# EtherMegaR3.net
KiCad netlist of a schematic drawn in EAGLE
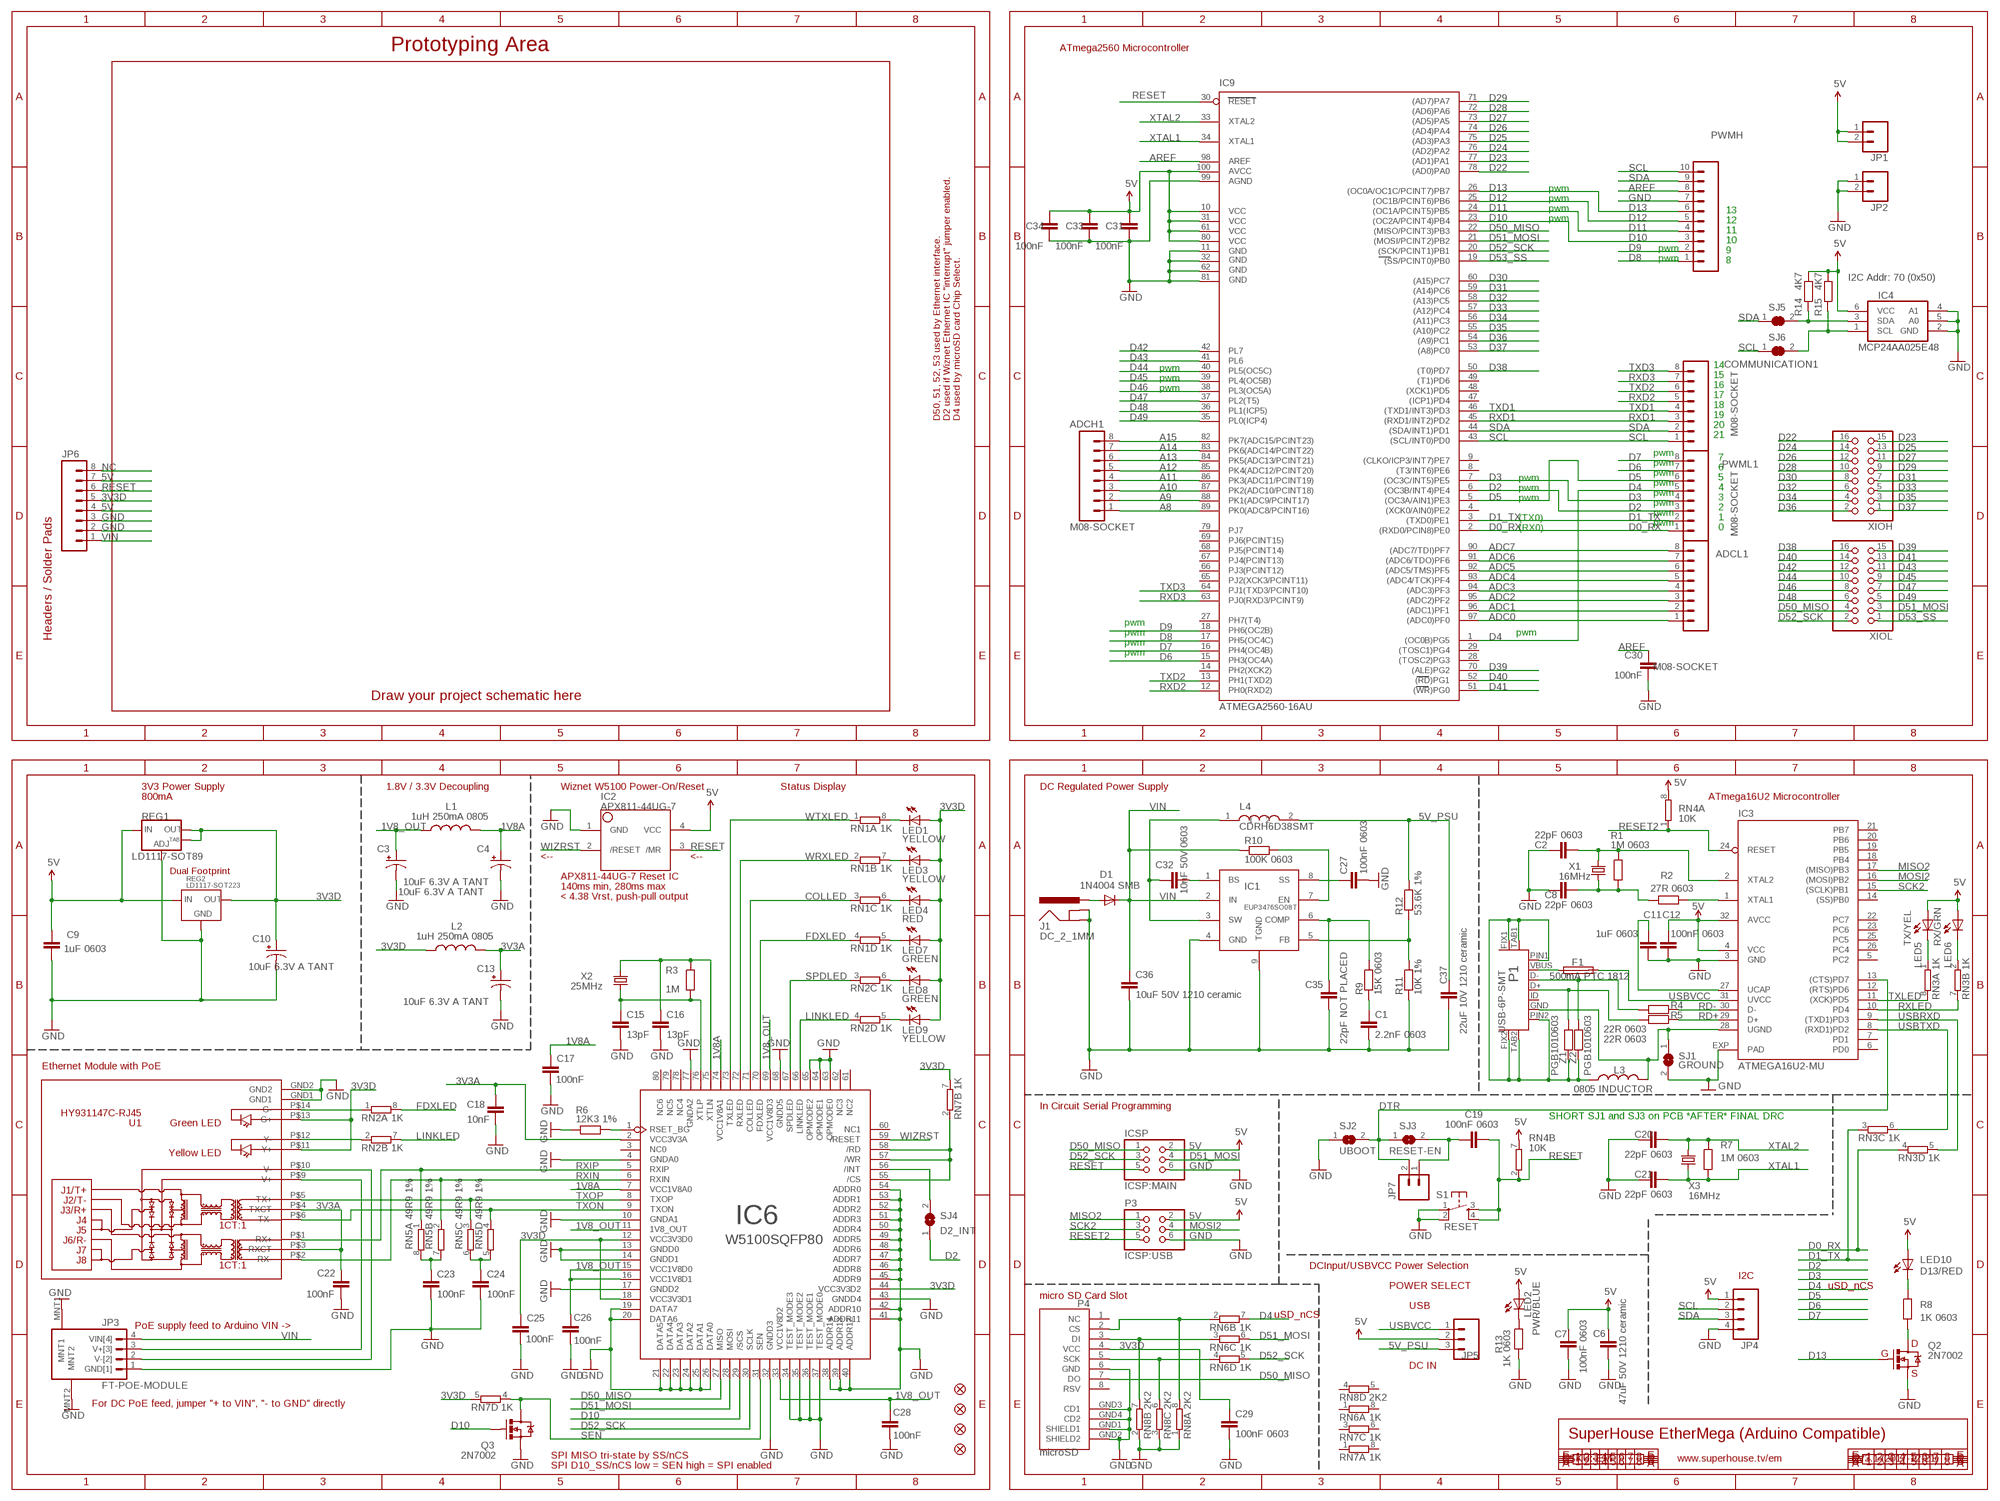
[diagram p0: schematic, sheet 1]

(export (version "E")
  (design (tool "Eeschema 10.0.6"))
  (components
    (comp (ref "ADCH1")
      (value "M08-SOCKET")
      (footprint "eagle-import:1X08-S")
      (libsource (lib "eagle-import") (part "M08-SOCKET"))
    )
    (comp (ref "ADCL1")
      (value "M08-SOCKET")
      (footprint "eagle-import:1X08-S")
      (libsource (lib "eagle-import") (part "M08-SOCKET"))
    )
    (comp (ref "C1")
      (value "2.2nF 0603")
      (footprint "eagle-import:C0603")
      (libsource (lib "eagle-import") (part "CAP0603"))
    )
    (comp (ref "C2")
      (value "22pF 0603")
      (footprint "eagle-import:C0603")
      (libsource (lib "eagle-import") (part "CAP0603"))
    )
    (comp (ref "C3")
      (value "10uF 6.3V A TANT")
      (footprint "eagle-import:EIA3216")
      (libsource (lib "eagle-import") (part "CAP_POL1206"))
    )
    (comp (ref "C4")
      (value "10uF 6.3V A TANT")
      (footprint "eagle-import:EIA3216")
      (libsource (lib "eagle-import") (part "CAP_POL1206"))
    )
    (comp (ref "C6")
      (value "47uF 50V 1210 ceramic")
      (footprint "eagle-import:C1210")
      (libsource (lib "eagle-import") (part "C-EUC1210"))
    )
    (comp (ref "C7")
      (value "100nF 0603")
      (footprint "eagle-import:C0603")
      (libsource (lib "eagle-import") (part "CAP0603"))
    )
    (comp (ref "C8")
      (value "22pF 0603")
      (footprint "eagle-import:C0603")
      (libsource (lib "eagle-import") (part "CAP0603"))
    )
    (comp (ref "C9")
      (value "1uF 0603")
      (footprint "eagle-import:C0603")
      (libsource (lib "eagle-import") (part "CAP0603"))
    )
    (comp (ref "C10")
      (value "10uF 6.3V A TANT")
      (footprint "eagle-import:EIA3216")
      (libsource (lib "eagle-import") (part "freetronics_CAP_POL1206"))
    )
    (comp (ref "C11")
      (value "1uF 0603")
      (footprint "eagle-import:C0603")
      (libsource (lib "eagle-import") (part "CAP0603"))
    )
    (comp (ref "C12")
      (value "100nF 0603")
      (footprint "eagle-import:C0603")
      (libsource (lib "eagle-import") (part "CAP0603"))
    )
    (comp (ref "C13")
      (value "10uF 6.3V A TANT")
      (footprint "eagle-import:EIA3216")
      (libsource (lib "eagle-import") (part "CAP_POL1206"))
    )
    (comp (ref "C15")
      (value "13pF")
      (footprint "eagle-import:C0603")
      (libsource (lib "eagle-import") (part "CAP0603"))
    )
    (comp (ref "C16")
      (value "13pF")
      (footprint "eagle-import:C0603")
      (libsource (lib "eagle-import") (part "CAP0603"))
    )
    (comp (ref "C17")
      (value "100nF")
      (footprint "eagle-import:C0603")
      (libsource (lib "eagle-import") (part "CAP0603"))
    )
    (comp (ref "C18")
      (value "10nF")
      (footprint "eagle-import:0603")
      (libsource (lib "eagle-import") (part "freetronics-marc_CAP0603"))
    )
    (comp (ref "C19")
      (value "100nF 0603")
      (footprint "eagle-import:C0603")
      (libsource (lib "eagle-import") (part "CAP0603"))
    )
    (comp (ref "C20")
      (value "22pF 0603")
      (footprint "eagle-import:C0603")
      (libsource (lib "eagle-import") (part "CAP0603"))
    )
    (comp (ref "C21")
      (value "22pF 0603")
      (footprint "eagle-import:C0603")
      (libsource (lib "eagle-import") (part "CAP0603"))
    )
    (comp (ref "C22")
      (value "100nF")
      (footprint "eagle-import:C0603")
      (libsource (lib "eagle-import") (part "CAP0603"))
    )
    (comp (ref "C23")
      (value "100nF")
      (footprint "eagle-import:C0603")
      (libsource (lib "eagle-import") (part "CAP0603"))
    )
    (comp (ref "C24")
      (value "100nF")
      (footprint "eagle-import:C0603")
      (libsource (lib "eagle-import") (part "CAP0603"))
    )
    (comp (ref "C25")
      (value "100nF")
      (footprint "eagle-import:C0603")
      (libsource (lib "eagle-import") (part "CAP0603"))
    )
    (comp (ref "C26")
      (value "100nF")
      (footprint "eagle-import:C0603")
      (libsource (lib "eagle-import") (part "CAP0603"))
    )
    (comp (ref "C27")
      (value "100nF 0603")
      (footprint "eagle-import:C0603")
      (libsource (lib "eagle-import") (part "CAP0603"))
    )
    (comp (ref "C28")
      (value "100nF")
      (footprint "eagle-import:C0603")
      (libsource (lib "eagle-import") (part "CAP0603"))
    )
    (comp (ref "C29")
      (value "100nF 0603")
      (footprint "eagle-import:C0603")
      (libsource (lib "eagle-import") (part "CAP0603"))
    )
    (comp (ref "C30")
      (value "100nF")
      (footprint "eagle-import:C0603")
      (libsource (lib "eagle-import") (part "CAP0603"))
    )
    (comp (ref "C31")
      (value "100nF")
      (footprint "eagle-import:C0603")
      (libsource (lib "eagle-import") (part "CAP0603"))
    )
    (comp (ref "C32")
      (value "10nF 50V 0603")
      (footprint "eagle-import:C0603")
      (libsource (lib "eagle-import") (part "CAP0603"))
    )
    (comp (ref "C33")
      (value "100nF")
      (footprint "eagle-import:C0603")
      (libsource (lib "eagle-import") (part "CAP0603"))
    )
    (comp (ref "C34")
      (value "100nF")
      (footprint "eagle-import:C0603")
      (libsource (lib "eagle-import") (part "CAP0603"))
    )
    (comp (ref "C35")
      (value "22pF NOT PLACED")
      (footprint "eagle-import:C0603")
      (libsource (lib "eagle-import") (part "CAP0603"))
    )
    (comp (ref "C36")
      (value "10uF 50V 1210 ceramic")
      (footprint "eagle-import:C1210")
      (libsource (lib "eagle-import") (part "C-EUC1210"))
    )
    (comp (ref "C37")
      (value "22uF 10V 1210 ceramic")
      (footprint "eagle-import:C1210")
      (libsource (lib "eagle-import") (part "C-EUC1210"))
    )
    (comp (ref "COMMUNICATION1")
      (value "M08-SOCKET")
      (footprint "eagle-import:1X08-S")
      (libsource (lib "eagle-import") (part "M08-SOCKET"))
    )
    (comp (ref "D1")
      (value "1N4004 SMB")
      (footprint "eagle-import:SMB-DIODE")
      (libsource (lib "eagle-import") (part "DIODESMB"))
    )
    (comp (ref "F1")
      (value "500mA PTC 1812")
      (footprint "eagle-import:1812")
      (libsource (lib "eagle-import") (part "PTC050"))
    )
    (comp (ref "FID1")
      (value "FIDUCIAL1X2.5")
      (footprint "eagle-import:FIDUCIAL-1X2.5")
      (libsource (lib "eagle-import") (part "FIDUCIAL1X2.5"))
    )
    (comp (ref "FID2")
      (value "FIDUCIAL1X2.5")
      (footprint "eagle-import:FIDUCIAL-1X2.5")
      (libsource (lib "eagle-import") (part "FIDUCIAL1X2.5"))
    )
    (comp (ref "FID3")
      (value "FIDUCIAL1X2.5")
      (footprint "eagle-import:FIDUCIAL-1X2.5")
      (libsource (lib "eagle-import") (part "FIDUCIAL1X2.5"))
    )
    (comp (ref "FID4")
      (value "FIDUCIAL1X2.5")
      (footprint "eagle-import:FIDUCIAL-1X2.5")
      (libsource (lib "eagle-import") (part "FIDUCIAL1X2.5"))
    )
    (comp (ref "IC1")
      (value "EUP3476SO08T")
      (footprint "eagle-import:SO08T")
      (libsource (lib "eagle-import") (part "EUP3476SO08T"))
    )
    (comp (ref "IC2")
      (value "APX811-44UG-7")
      (footprint "eagle-import:SOT143-R")
      (libsource (lib "eagle-import") (part "APX81X-RESET-IC"))
    )
    (comp (ref "IC3")
      (value "ATMEGA16U2-MU")
      (footprint "eagle-import:ATMEL_QFN32")
      (libsource (lib "eagle-import") (part "ATMEGA8U2QFN"))
    )
    (comp (ref "IC4")
      (value "MCP24AA025E48")
      (footprint "eagle-import:SOT23-6")
      (libsource (lib "eagle-import") (part "MCP24AA025E48"))
    )
    (comp (ref "IC6")
      (value "W5100SQFP80")
      (footprint "eagle-import:SQFP80")
      (libsource (lib "eagle-import") (part "W5100SQFP80"))
    )
    (comp (ref "IC9")
      (value "ATMEGA2560-16AU")
      (footprint "eagle-import:TQFP100")
      (libsource (lib "eagle-import") (part "ATMEGAAU1280-16"))
    )
    (comp (ref "ICSP")
      (value "ICSP:MAIN")
      (footprint "eagle-import:2X03")
      (libsource (lib "eagle-import") (part "PINHD-2X3"))
    )
    (comp (ref "J1")
      (value "DC_2_1MM")
      (footprint "eagle-import:POWER_JACK_SLOTS")
      (libsource (lib "eagle-import") (part "POWER_JACK-SLOTS"))
    )
    (comp (ref "JP1")
      (value "M02PTH")
      (footprint "eagle-import:1X02")
      (libsource (lib "eagle-import") (part "M02PTH"))
    )
    (comp (ref "JP2")
      (value "M02PTH")
      (footprint "eagle-import:1X02")
      (libsource (lib "eagle-import") (part "M02PTH"))
    )
    (comp (ref "JP3")
      (value "FT-POE-MODULE")
      (footprint "eagle-import:FT-POE-MODULE-CLEAN")
      (libsource (lib "eagle-import") (part "FT-POE-MODULE2"))
    )
    (comp (ref "JP4")
      (value "M04PTH")
      (footprint "eagle-import:1X04")
      (libsource (lib "eagle-import") (part "M04PTH"))
    )
    (comp (ref "JP5")
      (value "M03-PIN")
      (footprint "eagle-import:1X03-P")
      (libsource (lib "eagle-import") (part "M03-PIN"))
    )
    (comp (ref "JP6")
      (value "M08STD")
      (footprint "eagle-import:1X08")
      (libsource (lib "eagle-import") (part "M08STD"))
    )
    (comp (ref "JP7")
      (value "M02PTH")
      (footprint "eagle-import:1X02")
      (libsource (lib "eagle-import") (part "freetronics-master-v1.1_M02PTH"))
    )
    (comp (ref "L1")
      (value "1uH 250mA 0805")
      (footprint "eagle-import:L2012C")
      (libsource (lib "eagle-import") (part "L-USL2012C"))
    )
    (comp (ref "L2")
      (value "1uH 250mA 0805")
      (footprint "eagle-import:L2012C")
      (libsource (lib "eagle-import") (part "L-USL2012C"))
    )
    (comp (ref "L3")
      (value "0805 INDUCTOR")
      (footprint "eagle-import:0805-LARGE")
      (libsource (lib "eagle-import") (part "INDUCTOR0805-LARGE"))
    )
    (comp (ref "L4")
      (value "CDRH6D38SMT")
      (footprint "eagle-import:CDRH")
      (libsource (lib "eagle-import") (part "CDRH6D38SMT"))
    )
    (comp (ref "LED1")
      (value "YELLOW")
      (footprint "eagle-import:LED-0603")
      (libsource (lib "eagle-import") (part "LED0603"))
    )
    (comp (ref "LED2")
      (value "PWR/BLUE")
      (footprint "eagle-import:LED-0603")
      (libsource (lib "eagle-import") (part "LED0603"))
    )
    (comp (ref "LED3")
      (value "YELLOW")
      (footprint "eagle-import:LED-0603")
      (libsource (lib "eagle-import") (part "LED0603"))
    )
    (comp (ref "LED4")
      (value "RED")
      (footprint "eagle-import:LED-0603")
      (libsource (lib "eagle-import") (part "LED0603"))
    )
    (comp (ref "LED5")
      (value "TX/YEL")
      (footprint "eagle-import:LED-0603")
      (libsource (lib "eagle-import") (part "LED0603"))
    )
    (comp (ref "LED6")
      (value "RX/GRN")
      (footprint "eagle-import:LED-0603")
      (libsource (lib "eagle-import") (part "LED0603"))
    )
    (comp (ref "LED7")
      (value "GREEN")
      (footprint "eagle-import:LED-0603")
      (libsource (lib "eagle-import") (part "LED0603"))
    )
    (comp (ref "LED8")
      (value "GREEN")
      (footprint "eagle-import:LED-0603")
      (libsource (lib "eagle-import") (part "LED0603"))
    )
    (comp (ref "LED9")
      (value "YELLOW")
      (footprint "eagle-import:LED-0603")
      (libsource (lib "eagle-import") (part "LED0603"))
    )
    (comp (ref "LED10")
      (value "D13/RED")
      (footprint "eagle-import:LED-0603")
      (libsource (lib "eagle-import") (part "LED0603"))
    )
    (comp (ref "P1")
      (value "USB-6P-SMT")
      (footprint "eagle-import:USB-MICROB-MB05PMXX")
      (libsource (lib "eagle-import") (part "USB-6P-SMT"))
    )
    (comp (ref "P3")
      (value "ICSP:USB")
      (footprint "eagle-import:2X03")
      (libsource (lib "eagle-import") (part "PINHD-2X3"))
    )
    (comp (ref "P4")
      (value "microSD")
      (footprint "eagle-import:MOLEX-SD-500901-003")
      (libsource (lib "eagle-import") (part "USD-SOCKETHINGE"))
    )
    (comp (ref "PWMH")
      (value "M100.1")
      (footprint "eagle-import:1X10")
      (libsource (lib "eagle-import") (part "M100.1"))
    )
    (comp (ref "PWML1")
      (value "M08-SOCKET")
      (footprint "eagle-import:1X08-S")
      (libsource (lib "eagle-import") (part "M08-SOCKET"))
    )
    (comp (ref "Q2")
      (value "2N7002")
      (footprint "eagle-import:SOT23-3")
      (libsource (lib "eagle-import") (part "MOSFET-NCHANNEL-233"))
    )
    (comp (ref "Q3")
      (value "2N7002")
      (footprint "eagle-import:SOT23-3")
      (libsource (lib "eagle-import") (part "MOSFET-NCHANNEL-233"))
    )
    (comp (ref "R1")
      (value "1M 0603")
      (footprint "eagle-import:R0603")
      (libsource (lib "eagle-import") (part "RESISTOR0603"))
    )
    (comp (ref "R2")
      (value "27R 0603")
      (footprint "eagle-import:R0603")
      (libsource (lib "eagle-import") (part "RESISTOR0603"))
    )
    (comp (ref "R3")
      (value "1M")
      (footprint "eagle-import:R0603")
      (libsource (lib "eagle-import") (part "RESISTOR0603"))
    )
    (comp (ref "R4")
      (value "22R 0603")
      (footprint "eagle-import:R0603")
      (libsource (lib "eagle-import") (part "RESISTOR0603"))
    )
    (comp (ref "R5")
      (value "22R 0603")
      (footprint "eagle-import:R0603")
      (libsource (lib "eagle-import") (part "RESISTOR0603"))
    )
    (comp (ref "R6")
      (value "12K3 1%")
      (footprint "eagle-import:R0603")
      (libsource (lib "eagle-import") (part "RESISTOR0603"))
    )
    (comp (ref "R7")
      (value "1M 0603")
      (footprint "eagle-import:R0603")
      (libsource (lib "eagle-import") (part "RESISTOR0603"))
    )
    (comp (ref "R8")
      (value "1K 0603")
      (footprint "eagle-import:R0603")
      (libsource (lib "eagle-import") (part "RESISTOR0603"))
    )
    (comp (ref "R9")
      (value "15K 0603")
      (footprint "eagle-import:R0603")
      (libsource (lib "eagle-import") (part "RESISTOR0603"))
    )
    (comp (ref "R10")
      (value "100K 0603")
      (footprint "eagle-import:R0603")
      (libsource (lib "eagle-import") (part "RESISTOR0603"))
    )
    (comp (ref "R11")
      (value "10K 1%")
      (footprint "eagle-import:R0603")
      (libsource (lib "eagle-import") (part "RESISTOR0603"))
    )
    (comp (ref "R12")
      (value "53.6K 1%")
      (footprint "eagle-import:0603")
      (libsource (lib "eagle-import") (part "freetronics-original_RESISTOR0603"))
    )
    (comp (ref "R13")
      (value "1K 0603")
      (footprint "eagle-import:R0603")
      (libsource (lib "eagle-import") (part "RESISTOR0603"))
    )
    (comp (ref "R14")
      (value "4K7")
      (footprint "eagle-import:R0603")
      (libsource (lib "eagle-import") (part "RESISTOR0603"))
    )
    (comp (ref "R15")
      (value "4K7")
      (footprint "eagle-import:R0603")
      (libsource (lib "eagle-import") (part "RESISTOR0603"))
    )
    (comp (ref "REG1")
      (value "LD1117-SOT89")
      (footprint "eagle-import:SOT89")
      (libsource (lib "eagle-import") (part "V_REG_LM1117SOT89"))
    )
    (comp (ref "REG2")
      (value "LD1117-SOT223")
      (footprint "eagle-import:SOT-223")
      (libsource (lib "eagle-import") (part "LD1117"))
    )
    (comp (ref "RN1")
      (value "1K")
      (footprint "eagle-import:CAY16")
      (libsource (lib "eagle-import") (part "4R-NCAY16"))
    )
    (comp (ref "RN2")
      (value "1K")
      (footprint "eagle-import:CAY16")
      (libsource (lib "eagle-import") (part "4R-NCAY16"))
    )
    (comp (ref "RN3")
      (value "1K")
      (footprint "eagle-import:CAY16")
      (libsource (lib "eagle-import") (part "4R-NCAY16"))
    )
    (comp (ref "RN4")
      (value "10K")
      (footprint "eagle-import:CAY16")
      (libsource (lib "eagle-import") (part "freetronics-master-v1_4R-NCAY16"))
    )
    (comp (ref "RN5")
      (value "49R9 1%")
      (footprint "eagle-import:CAY16")
      (libsource (lib "eagle-import") (part "4R-NCAY16"))
    )
    (comp (ref "RN6")
      (value "1K")
      (footprint "eagle-import:CAY16")
      (libsource (lib "eagle-import") (part "4R-NCAY16"))
    )
    (comp (ref "RN7")
      (value "1K")
      (footprint "eagle-import:CAY16")
      (libsource (lib "eagle-import") (part "4R-NCAY16"))
    )
    (comp (ref "RN8")
      (value "2K2")
      (footprint "eagle-import:CAY16")
      (libsource (lib "eagle-import") (part "4R-NCAY16"))
    )
    (comp (ref "S1")
      (value "RESET")
      (footprint "eagle-import:TACTILE_SMD-6MM")
      (libsource (lib "eagle-import") (part "TAC_SWITCH-SMT-6"))
    )
    (comp (ref "SJ1")
      (value "GROUND")
      (footprint "eagle-import:SJ")
      (libsource (lib "eagle-import") (part "SJ"))
    )
    (comp (ref "SJ2")
      (value "UBOOT")
      (footprint "eagle-import:SJ")
      (libsource (lib "eagle-import") (part "SJ"))
    )
    (comp (ref "SJ3")
      (value "RESET-EN")
      (footprint "eagle-import:SJ")
      (libsource (lib "eagle-import") (part "SJ"))
    )
    (comp (ref "SJ4")
      (value "D2_INT")
      (footprint "eagle-import:SJ")
      (libsource (lib "eagle-import") (part "SJ"))
    )
    (comp (ref "SJ5")
      (value "SJCN")
      (footprint "eagle-import:SJC")
      (libsource (lib "eagle-import") (part "SJCN"))
    )
    (comp (ref "SJ6")
      (value "SJCN")
      (footprint "eagle-import:SJC")
      (libsource (lib "eagle-import") (part "SJCN"))
    )
    (comp (ref "U1")
      (value "HY931147C-RJ45")
      (footprint "eagle-import:HY931147C")
      (libsource (lib "eagle-import") (part "HY931147C-RJ45"))
    )
    (comp (ref "X1")
      (value "16MHz")
      (footprint "eagle-import:HC49U-V")
      (libsource (lib "eagle-import") (part "CRYSTALHC49UV"))
    )
    (comp (ref "X2")
      (value "25MHz")
      (footprint "eagle-import:HC49U-V")
      (libsource (lib "eagle-import") (part "CRYSTALHC49UV"))
    )
    (comp (ref "X3")
      (value "16MHz")
      (footprint "eagle-import:HC49U-V")
      (libsource (lib "eagle-import") (part "CRYSTALHC49UV"))
    )
    (comp (ref "XIOH")
      (value "PINHD-2X8")
      (footprint "eagle-import:2X08")
      (libsource (lib "eagle-import") (part "PINHD-2X8"))
    )
    (comp (ref "XIOL")
      (value "PINHD-2X8")
      (footprint "eagle-import:2X08")
      (libsource (lib "eagle-import") (part "PINHD-2X8"))
    )
    (comp (ref "Z1")
      (value "PGB1010603")
      (footprint "eagle-import:0603")
      (libsource (lib "eagle-import") (part "freetronics_RESISTOR0603"))
    )
    (comp (ref "Z2")
      (value "PGB1010603")
      (footprint "eagle-import:0603")
      (libsource (lib "eagle-import") (part "freetronics_RESISTOR0603"))
    )
  )
  (nets
    (net (code "1") (name "/1V8A") (class "Default")
      (node (ref "C17") (pin "1") (pinfunction "1_1") (pintype "passive"))
      (node (ref "C4") (pin "A") (pinfunction "+_A") (pintype "passive"))
      (node (ref "IC6") (pin "7") (pinfunction "VCC1V8A0_7") (pintype "bidirectional"))
      (node (ref "IC6") (pin "74") (pinfunction "VCC1V8A1_74") (pintype "bidirectional"))
      (node (ref "L1") (pin "2") (pinfunction "2_2") (pintype "passive"))
    )
    (net (code "2") (name "/1V8_OUT") (class "Default")
      (node (ref "C26") (pin "1") (pinfunction "1_1") (pintype "passive"))
      (node (ref "C28") (pin "1") (pinfunction "1_1") (pintype "passive"))
      (node (ref "C3") (pin "A") (pinfunction "+_A") (pintype "passive"))
      (node (ref "IC6") (pin "11") (pinfunction "1V8_OUT_11") (pintype "bidirectional"))
      (node (ref "IC6") (pin "15") (pinfunction "VCC1V8D0_15") (pintype "bidirectional"))
      (node (ref "IC6") (pin "16") (pinfunction "VCC1V8D1_16") (pintype "bidirectional"))
      (node (ref "IC6") (pin "33") (pinfunction "VCC1V8D2_33") (pintype "bidirectional"))
      (node (ref "IC6") (pin "69") (pinfunction "VCC1V8D3_69") (pintype "bidirectional"))
      (node (ref "L1") (pin "1") (pinfunction "1_1") (pintype "passive"))
    )
    (net (code "3") (name "/3V3A") (class "Default")
      (node (ref "C13") (pin "A") (pinfunction "+_A") (pintype "passive"))
      (node (ref "C18") (pin "1") (pinfunction "1_1") (pintype "passive"))
      (node (ref "C22") (pin "1") (pinfunction "1_1") (pintype "passive"))
      (node (ref "IC6") (pin "2") (pinfunction "VCC3V3A_2") (pintype "bidirectional"))
      (node (ref "L2") (pin "2") (pinfunction "2_2") (pintype "passive"))
      (node (ref "U1") (pin "P$3") (pinfunction "RXCT_P$3") (pintype "bidirectional"))
      (node (ref "U1") (pin "P$4") (pinfunction "TXCT_P$4") (pintype "bidirectional"))
    )
    (net (code "4") (name "/3V3D") (class "Default")
      (node (ref "C10") (pin "A") (pinfunction "+_A") (pintype "passive"))
      (node (ref "C25") (pin "1") (pinfunction "1_1") (pintype "passive"))
      (node (ref "C29") (pin "1") (pinfunction "1_1") (pintype "passive"))
      (node (ref "IC6") (pin "12") (pinfunction "VCC3V3D0_12") (pintype "bidirectional"))
      (node (ref "IC6") (pin "18") (pinfunction "VCC3V3D1_18") (pintype "bidirectional"))
      (node (ref "IC6") (pin "44") (pinfunction "VCC3V3D2_44") (pintype "bidirectional"))
      (node (ref "JP6") (pin "5") (pinfunction "5_5") (pintype "passive"))
      (node (ref "L2") (pin "1") (pinfunction "1_1") (pintype "passive"))
      (node (ref "LED1") (pin "A") (pinfunction "A_A") (pintype "passive"))
      (node (ref "LED3") (pin "A") (pinfunction "A_A") (pintype "passive"))
      (node (ref "LED4") (pin "A") (pinfunction "A_A") (pintype "passive"))
      (node (ref "LED7") (pin "A") (pinfunction "A_A") (pintype "passive"))
      (node (ref "LED8") (pin "A") (pinfunction "A_A") (pintype "passive"))
      (node (ref "LED9") (pin "A") (pinfunction "A_A") (pintype "passive"))
      (node (ref "P4") (pin "4") (pinfunction "VCC_4") (pintype "bidirectional"))
      (node (ref "REG1") (pin "2") (pinfunction "OUT_2") (pintype "output"))
      (node (ref "REG1") (pin "4") (pinfunction "OUT_4") (pintype "output"))
      (node (ref "REG2") (pin "2") (pinfunction "OUT_2") (pintype "power_in"))
      (node (ref "REG2") (pin "4") (pinfunction "OUT_4") (pintype "power_in"))
      (node (ref "RN7") (pin "5") (pinfunction "2_5") (pintype "passive"))
      (node (ref "RN7") (pin "7") (pinfunction "2_7") (pintype "passive"))
      (node (ref "U1") (pin "P$11") (pinfunction "Y+_P$11") (pintype "bidirectional"))
      (node (ref "U1") (pin "P$13") (pinfunction "G+_P$13") (pintype "bidirectional"))
    )
    (net (code "5") (name "/5V_PSU") (class "Default")
      (node (ref "C37") (pin "1") (pinfunction "1_1") (pintype "passive"))
      (node (ref "JP5") (pin "3") (pinfunction "3_3") (pintype "passive"))
      (node (ref "L4") (pin "2") (pinfunction "2_2") (pintype "bidirectional"))
      (node (ref "R12") (pin "2") (pinfunction "2_2") (pintype "passive"))
    )
    (net (code "6") (name "/A8") (class "Default")
      (node (ref "ADCH1") (pin "1") (pinfunction "1_1") (pintype "passive"))
      (node (ref "IC9") (pin "89") (pinfunction "PK0(ADC8/PCINT16)_89") (pintype "bidirectional"))
    )
    (net (code "7") (name "/A9") (class "Default")
      (node (ref "ADCH1") (pin "2") (pinfunction "2_2") (pintype "passive"))
      (node (ref "IC9") (pin "88") (pinfunction "PK1(ADC9/PCINT17)_88") (pintype "bidirectional"))
    )
    (net (code "8") (name "/A10") (class "Default")
      (node (ref "ADCH1") (pin "3") (pinfunction "3_3") (pintype "passive"))
      (node (ref "IC9") (pin "87") (pinfunction "PK2(ADC10/PCINT18)_87") (pintype "bidirectional"))
    )
    (net (code "9") (name "/A11") (class "Default")
      (node (ref "ADCH1") (pin "4") (pinfunction "4_4") (pintype "passive"))
      (node (ref "IC9") (pin "86") (pinfunction "PK3(ADC11/PCINT19)_86") (pintype "bidirectional"))
    )
    (net (code "10") (name "/A12") (class "Default")
      (node (ref "ADCH1") (pin "5") (pinfunction "5_5") (pintype "passive"))
      (node (ref "IC9") (pin "85") (pinfunction "PK4(ADC12/PCINT20)_85") (pintype "bidirectional"))
    )
    (net (code "11") (name "/A13") (class "Default")
      (node (ref "ADCH1") (pin "6") (pinfunction "6_6") (pintype "passive"))
      (node (ref "IC9") (pin "84") (pinfunction "PK5(ADC13/PCINT21)_84") (pintype "bidirectional"))
    )
    (net (code "12") (name "/A14") (class "Default")
      (node (ref "ADCH1") (pin "7") (pinfunction "7_7") (pintype "passive"))
      (node (ref "IC9") (pin "83") (pinfunction "PK6(ADC14/PCINT22)_83") (pintype "bidirectional"))
    )
    (net (code "13") (name "/A15") (class "Default")
      (node (ref "ADCH1") (pin "8") (pinfunction "8_8") (pintype "passive"))
      (node (ref "IC9") (pin "82") (pinfunction "PK7(ADC15/PCINT23)_82") (pintype "bidirectional"))
    )
    (net (code "14") (name "/ADC0") (class "Default")
      (node (ref "ADCL1") (pin "1") (pinfunction "1_1") (pintype "passive"))
      (node (ref "IC9") (pin "97") (pinfunction "(ADC0)PF0_97") (pintype "bidirectional"))
    )
    (net (code "15") (name "/ADC1") (class "Default")
      (node (ref "ADCL1") (pin "2") (pinfunction "2_2") (pintype "passive"))
      (node (ref "IC9") (pin "96") (pinfunction "(ADC1)PF1_96") (pintype "bidirectional"))
    )
    (net (code "16") (name "/ADC2") (class "Default")
      (node (ref "ADCL1") (pin "3") (pinfunction "3_3") (pintype "passive"))
      (node (ref "IC9") (pin "95") (pinfunction "(ADC2)PF2_95") (pintype "bidirectional"))
    )
    (net (code "17") (name "/ADC3") (class "Default")
      (node (ref "ADCL1") (pin "4") (pinfunction "4_4") (pintype "passive"))
      (node (ref "IC9") (pin "94") (pinfunction "(ADC3)PF3_94") (pintype "bidirectional"))
    )
    (net (code "18") (name "/ADC4") (class "Default")
      (node (ref "ADCL1") (pin "5") (pinfunction "5_5") (pintype "passive"))
      (node (ref "IC9") (pin "93") (pinfunction "(ADC4/TCK)PF4_93") (pintype "bidirectional"))
    )
    (net (code "19") (name "/ADC5") (class "Default")
      (node (ref "ADCL1") (pin "6") (pinfunction "6_6") (pintype "passive"))
      (node (ref "IC9") (pin "92") (pinfunction "(ADC5/TMS)PF5_92") (pintype "bidirectional"))
    )
    (net (code "20") (name "/ADC6") (class "Default")
      (node (ref "ADCL1") (pin "7") (pinfunction "7_7") (pintype "passive"))
      (node (ref "IC9") (pin "91") (pinfunction "(ADC6/TDO)PF6_91") (pintype "bidirectional"))
    )
    (net (code "21") (name "/ADC7") (class "Default")
      (node (ref "ADCL1") (pin "8") (pinfunction "8_8") (pintype "passive"))
      (node (ref "IC9") (pin "90") (pinfunction "(ADC7/TDI)PF7_90") (pintype "bidirectional"))
    )
    (net (code "22") (name "/AREF") (class "Default")
      (node (ref "C30") (pin "1") (pinfunction "1_1") (pintype "passive"))
      (node (ref "IC9") (pin "98") (pinfunction "AREF_98") (pintype "bidirectional"))
      (node (ref "PWMH") (pin "8") (pinfunction "8_8") (pintype "passive"))
    )
    (net (code "23") (name "/COLLED") (class "Default")
      (node (ref "IC6") (pin "71") (pinfunction "COLLED_71") (pintype "bidirectional"))
      (node (ref "RN1") (pin "3") (pinfunction "1_3") (pintype "passive"))
    )
    (net (code "24") (name "/D0_RX") (class "Default")
      (node (ref "IC9") (pin "2") (pinfunction "(RXD0/PCIN8)PE0_2") (pintype "bidirectional"))
      (node (ref "PWML1") (pin "1") (pinfunction "1_1") (pintype "passive"))
      (node (ref "RN3") (pin "4") (pinfunction "1_4") (pintype "passive"))
    )
    (net (code "25") (name "/D1_TX") (class "Default")
      (node (ref "IC9") (pin "3") (pinfunction "(TXD0)PE1_3") (pintype "bidirectional"))
      (node (ref "PWML1") (pin "2") (pinfunction "2_2") (pintype "passive"))
      (node (ref "RN3") (pin "3") (pinfunction "1_3") (pintype "passive"))
    )
    (net (code "26") (name "/D2") (class "Default")
      (node (ref "IC9") (pin "6") (pinfunction "(OC3B/INT4)PE4_6") (pintype "bidirectional"))
      (node (ref "PWML1") (pin "3") (pinfunction "3_3") (pintype "passive"))
      (node (ref "SJ4") (pin "1") (pinfunction "1_1") (pintype "passive"))
    )
    (net (code "27") (name "/D3") (class "Default")
      (node (ref "IC9") (pin "7") (pinfunction "(OC3C/INT5)PE5_7") (pintype "bidirectional"))
      (node (ref "PWML1") (pin "4") (pinfunction "4_4") (pintype "passive"))
    )
    (net (code "28") (name "/D4") (class "Default")
      (node (ref "IC9") (pin "1") (pinfunction "(OC0B)PG5_1") (pintype "bidirectional"))
      (node (ref "PWML1") (pin "5") (pinfunction "5_5") (pintype "passive"))
      (node (ref "RN6") (pin "7") (pinfunction "2_7") (pintype "passive"))
    )
    (net (code "29") (name "/D5") (class "Default")
      (node (ref "IC9") (pin "5") (pinfunction "(OC3A/AIN1)PE3_5") (pintype "bidirectional"))
      (node (ref "PWML1") (pin "6") (pinfunction "6_6") (pintype "passive"))
    )
    (net (code "30") (name "/D6") (class "Default")
      (node (ref "IC9") (pin "15") (pinfunction "PH3(OC4A)_15") (pintype "bidirectional"))
      (node (ref "PWML1") (pin "7") (pinfunction "7_7") (pintype "passive"))
    )
    (net (code "31") (name "/D7") (class "Default")
      (node (ref "IC9") (pin "16") (pinfunction "PH4(OC4B)_16") (pintype "bidirectional"))
      (node (ref "PWML1") (pin "8") (pinfunction "8_8") (pintype "passive"))
    )
    (net (code "32") (name "/D8") (class "Default")
      (node (ref "IC9") (pin "17") (pinfunction "PH5(OC4C)_17") (pintype "bidirectional"))
      (node (ref "PWMH") (pin "1") (pinfunction "1_1") (pintype "passive"))
    )
    (net (code "33") (name "/D9") (class "Default")
      (node (ref "IC9") (pin "18") (pinfunction "PH6(OC2B)_18") (pintype "bidirectional"))
      (node (ref "PWMH") (pin "2") (pinfunction "2_2") (pintype "passive"))
    )
    (net (code "34") (name "/D10") (class "Default")
      (node (ref "IC6") (pin "29") (pinfunction "/SCS_29") (pintype "bidirectional"))
      (node (ref "IC9") (pin "23") (pinfunction "(OC2A/PCINT4)PB4_23") (pintype "bidirectional"))
      (node (ref "PWMH") (pin "3") (pinfunction "3_3") (pintype "passive"))
      (node (ref "Q3") (pin "1") (pinfunction "G_1") (pintype "passive"))
    )
    (net (code "35") (name "/D11") (class "Default")
      (node (ref "IC9") (pin "24") (pinfunction "(OC1A/PCINT5)PB5_24") (pintype "bidirectional"))
      (node (ref "PWMH") (pin "4") (pinfunction "4_4") (pintype "passive"))
    )
    (net (code "36") (name "/D12") (class "Default")
      (node (ref "IC9") (pin "25") (pinfunction "(OC1B/PCINT6)PB6_25") (pintype "bidirectional"))
      (node (ref "PWMH") (pin "5") (pinfunction "5_5") (pintype "passive"))
    )
    (net (code "37") (name "/D13") (class "Default")
      (node (ref "IC9") (pin "26") (pinfunction "(OC0A/OC1C/PCINT7)PB7_26") (pintype "bidirectional"))
      (node (ref "PWMH") (pin "6") (pinfunction "6_6") (pintype "passive"))
      (node (ref "Q2") (pin "1") (pinfunction "G_1") (pintype "passive"))
    )
    (net (code "38") (name "/D22") (class "Default")
      (node (ref "IC9") (pin "78") (pinfunction "(AD0)PA0_78") (pintype "bidirectional"))
      (node (ref "XIOH") (pin "16") (pinfunction "16_16") (pintype "passive"))
    )
    (net (code "39") (name "/D23") (class "Default")
      (node (ref "IC9") (pin "77") (pinfunction "(AD1)PA1_77") (pintype "bidirectional"))
      (node (ref "XIOH") (pin "15") (pinfunction "15_15") (pintype "passive"))
    )
    (net (code "40") (name "/D24") (class "Default")
      (node (ref "IC9") (pin "76") (pinfunction "(AD2)PA2_76") (pintype "bidirectional"))
      (node (ref "XIOH") (pin "14") (pinfunction "14_14") (pintype "passive"))
    )
    (net (code "41") (name "/D25") (class "Default")
      (node (ref "IC9") (pin "75") (pinfunction "(AD3)PA3_75") (pintype "bidirectional"))
      (node (ref "XIOH") (pin "13") (pinfunction "13_13") (pintype "passive"))
    )
    (net (code "42") (name "/D26") (class "Default")
      (node (ref "IC9") (pin "74") (pinfunction "(AD4)PA4_74") (pintype "bidirectional"))
      (node (ref "XIOH") (pin "12") (pinfunction "12_12") (pintype "passive"))
    )
    (net (code "43") (name "/D27") (class "Default")
      (node (ref "IC9") (pin "73") (pinfunction "(AD5)PA5_73") (pintype "bidirectional"))
      (node (ref "XIOH") (pin "11") (pinfunction "11_11") (pintype "passive"))
    )
    (net (code "44") (name "/D28") (class "Default")
      (node (ref "IC9") (pin "72") (pinfunction "(AD6)PA6_72") (pintype "bidirectional"))
      (node (ref "XIOH") (pin "10") (pinfunction "10_10") (pintype "passive"))
    )
    (net (code "45") (name "/D29") (class "Default")
      (node (ref "IC9") (pin "71") (pinfunction "(AD7)PA7_71") (pintype "bidirectional"))
      (node (ref "XIOH") (pin "9") (pinfunction "9_9") (pintype "passive"))
    )
    (net (code "46") (name "/D30") (class "Default")
      (node (ref "IC9") (pin "60") (pinfunction "(A15)PC7_60") (pintype "bidirectional"))
      (node (ref "XIOH") (pin "8") (pinfunction "8_8") (pintype "passive"))
    )
    (net (code "47") (name "/D31") (class "Default")
      (node (ref "IC9") (pin "59") (pinfunction "(A14)PC6_59") (pintype "bidirectional"))
      (node (ref "XIOH") (pin "7") (pinfunction "7_7") (pintype "passive"))
    )
    (net (code "48") (name "/D32") (class "Default")
      (node (ref "IC9") (pin "58") (pinfunction "(A13)PC5_58") (pintype "bidirectional"))
      (node (ref "XIOH") (pin "6") (pinfunction "6_6") (pintype "passive"))
    )
    (net (code "49") (name "/D33") (class "Default")
      (node (ref "IC9") (pin "57") (pinfunction "(A12)PC4_57") (pintype "bidirectional"))
      (node (ref "XIOH") (pin "5") (pinfunction "5_5") (pintype "passive"))
    )
    (net (code "50") (name "/D34") (class "Default")
      (node (ref "IC9") (pin "56") (pinfunction "(A11)PC3_56") (pintype "bidirectional"))
      (node (ref "XIOH") (pin "4") (pinfunction "4_4") (pintype "passive"))
    )
    (net (code "51") (name "/D35") (class "Default")
      (node (ref "IC9") (pin "55") (pinfunction "(A10)PC2_55") (pintype "bidirectional"))
      (node (ref "XIOH") (pin "3") (pinfunction "3_3") (pintype "passive"))
    )
    (net (code "52") (name "/D36") (class "Default")
      (node (ref "IC9") (pin "54") (pinfunction "(A9)PC1_54") (pintype "bidirectional"))
      (node (ref "XIOH") (pin "2") (pinfunction "2_2") (pintype "passive"))
    )
    (net (code "53") (name "/D37") (class "Default")
      (node (ref "IC9") (pin "53") (pinfunction "(A8)PC0_53") (pintype "bidirectional"))
      (node (ref "XIOH") (pin "1") (pinfunction "1_1") (pintype "passive"))
    )
    (net (code "54") (name "/D38") (class "Default")
      (node (ref "IC9") (pin "50") (pinfunction "(T0)PD7_50") (pintype "bidirectional"))
      (node (ref "XIOL") (pin "16") (pinfunction "16_16") (pintype "passive"))
    )
    (net (code "55") (name "/D39") (class "Default")
      (node (ref "IC9") (pin "70") (pinfunction "(ALE)PG2_70") (pintype "bidirectional"))
      (node (ref "XIOL") (pin "15") (pinfunction "15_15") (pintype "passive"))
    )
    (net (code "56") (name "/D40") (class "Default")
      (node (ref "IC9") (pin "52") (pinfunction "(RD)PG1_52") (pintype "bidirectional"))
      (node (ref "XIOL") (pin "14") (pinfunction "14_14") (pintype "passive"))
    )
    (net (code "57") (name "/D41") (class "Default")
      (node (ref "IC9") (pin "51") (pinfunction "(WR)PG0_51") (pintype "bidirectional"))
      (node (ref "XIOL") (pin "13") (pinfunction "13_13") (pintype "passive"))
    )
    (net (code "58") (name "/D42") (class "Default")
      (node (ref "IC9") (pin "42") (pinfunction "PL7_42") (pintype "bidirectional"))
      (node (ref "XIOL") (pin "12") (pinfunction "12_12") (pintype "passive"))
    )
    (net (code "59") (name "/D43") (class "Default")
      (node (ref "IC9") (pin "41") (pinfunction "PL6_41") (pintype "bidirectional"))
      (node (ref "XIOL") (pin "11") (pinfunction "11_11") (pintype "passive"))
    )
    (net (code "60") (name "/D44") (class "Default")
      (node (ref "IC9") (pin "40") (pinfunction "PL5(OC5C)_40") (pintype "bidirectional"))
      (node (ref "XIOL") (pin "10") (pinfunction "10_10") (pintype "passive"))
    )
    (net (code "61") (name "/D45") (class "Default")
      (node (ref "IC9") (pin "39") (pinfunction "PL4(OC5B)_39") (pintype "bidirectional"))
      (node (ref "XIOL") (pin "9") (pinfunction "9_9") (pintype "passive"))
    )
    (net (code "62") (name "/D46") (class "Default")
      (node (ref "IC9") (pin "38") (pinfunction "PL3(OC5A)_38") (pintype "bidirectional"))
      (node (ref "XIOL") (pin "8") (pinfunction "8_8") (pintype "passive"))
    )
    (net (code "63") (name "/D47") (class "Default")
      (node (ref "IC9") (pin "37") (pinfunction "PL2(T5)_37") (pintype "bidirectional"))
      (node (ref "XIOL") (pin "7") (pinfunction "7_7") (pintype "passive"))
    )
    (net (code "64") (name "/D48") (class "Default")
      (node (ref "IC9") (pin "36") (pinfunction "PL1(ICP5)_36") (pintype "bidirectional"))
      (node (ref "XIOL") (pin "6") (pinfunction "6_6") (pintype "passive"))
    )
    (net (code "65") (name "/D49") (class "Default")
      (node (ref "IC9") (pin "35") (pinfunction "PL0(ICP4)_35") (pintype "bidirectional"))
      (node (ref "XIOL") (pin "5") (pinfunction "5_5") (pintype "passive"))
    )
    (net (code "66") (name "/D50_MISO") (class "Default")
      (node (ref "IC6") (pin "27") (pinfunction "MISO_27") (pintype "bidirectional"))
      (node (ref "IC9") (pin "22") (pinfunction "(MISO/PCINT3)PB3_22") (pintype "bidirectional"))
      (node (ref "ICSP") (pin "1") (pinfunction "1_1") (pintype "passive"))
      (node (ref "P4") (pin "7") (pinfunction "DO_7") (pintype "bidirectional"))
      (node (ref "XIOL") (pin "4") (pinfunction "4_4") (pintype "passive"))
    )
    (net (code "67") (name "/D51_MOSI") (class "Default")
      (node (ref "IC6") (pin "28") (pinfunction "MOSI_28") (pintype "bidirectional"))
      (node (ref "IC9") (pin "21") (pinfunction "(MOSI/PCINT2)PB2_21") (pintype "bidirectional"))
      (node (ref "ICSP") (pin "4") (pinfunction "4_4") (pintype "passive"))
      (node (ref "RN6") (pin "6") (pinfunction "2_6") (pintype "passive"))
      (node (ref "XIOL") (pin "3") (pinfunction "3_3") (pintype "passive"))
    )
    (net (code "68") (name "/D52_SCK") (class "Default")
      (node (ref "IC6") (pin "30") (pinfunction "SCLK_30") (pintype "bidirectional"))
      (node (ref "IC9") (pin "20") (pinfunction "(SCK/PCINT1)PB1_20") (pintype "bidirectional"))
      (node (ref "ICSP") (pin "3") (pinfunction "3_3") (pintype "passive"))
      (node (ref "RN6") (pin "5") (pinfunction "2_5") (pintype "passive"))
      (node (ref "XIOL") (pin "2") (pinfunction "2_2") (pintype "passive"))
    )
    (net (code "69") (name "/D53_SS") (class "Default")
      (node (ref "IC9") (pin "19") (pinfunction "(SS/PCINT0)PB0_19") (pintype "bidirectional"))
      (node (ref "XIOL") (pin "1") (pinfunction "1_1") (pintype "passive"))
    )
    (net (code "70") (name "/DTR") (class "Default")
      (node (ref "IC3") (pin "13") (pinfunction "(CTS)PD7_13") (pintype "bidirectional"))
      (node (ref "JP7") (pin "2") (pinfunction "2_2") (pintype "passive"))
      (node (ref "SJ2") (pin "2") (pinfunction "2_2") (pintype "passive"))
      (node (ref "SJ3") (pin "1") (pinfunction "1_1") (pintype "passive"))
    )
    (net (code "71") (name "/FDXLED") (class "Default")
      (node (ref "IC6") (pin "70") (pinfunction "FDXLED_70") (pintype "bidirectional"))
      (node (ref "RN1") (pin "4") (pinfunction "1_4") (pintype "passive"))
      (node (ref "RN2") (pin "8") (pinfunction "2_8") (pintype "passive"))
    )
    (net (code "72") (name "/LINKLED") (class "Default")
      (node (ref "IC6") (pin "66") (pinfunction "LINKLED_66") (pintype "bidirectional"))
      (node (ref "RN2") (pin "4") (pinfunction "1_4") (pintype "passive"))
      (node (ref "RN2") (pin "7") (pinfunction "2_7") (pintype "passive"))
    )
    (net (code "73") (name "/MISO2") (class "Default")
      (node (ref "IC3") (pin "17") (pinfunction "(MISO)PB3_17") (pintype "bidirectional"))
      (node (ref "P3") (pin "1") (pinfunction "1_1") (pintype "passive"))
    )
    (net (code "74") (name "/MOSI2") (class "Default")
      (node (ref "IC3") (pin "16") (pinfunction "(MOSI)PB2_16") (pintype "bidirectional"))
      (node (ref "P3") (pin "4") (pinfunction "4_4") (pintype "passive"))
    )
    (net (code "75") (name "/NC") (class "Default")
      (node (ref "JP6") (pin "8") (pinfunction "8_8") (pintype "passive"))
    )
    (net (code "76") (name "/RD+") (class "Default")
      (node (ref "IC3") (pin "29") (pinfunction "D+_29") (pintype "bidirectional"))
      (node (ref "R5") (pin "1") (pinfunction "1_1") (pintype "passive"))
    )
    (net (code "77") (name "/RD-") (class "Default")
      (node (ref "IC3") (pin "30") (pinfunction "D-_30") (pintype "bidirectional"))
      (node (ref "R4") (pin "1") (pinfunction "1_1") (pintype "passive"))
    )
    (net (code "78") (name "/RESET") (class "Default")
      (node (ref "C19") (pin "2") (pinfunction "2_2") (pintype "passive"))
      (node (ref "IC2") (pin "3") (pinfunction "/MR_3") (pintype "input"))
      (node (ref "IC9") (pin "30") (pinfunction "RESET_30") (pintype "input"))
      (node (ref "ICSP") (pin "5") (pinfunction "5_5") (pintype "passive"))
      (node (ref "JP6") (pin "6") (pinfunction "6_6") (pintype "passive"))
      (node (ref "RN4") (pin "2") (pinfunction "1_2") (pintype "passive"))
      (node (ref "S1") (pin "3") (pinfunction "3_3") (pintype "passive"))
      (node (ref "S1") (pin "4") (pinfunction "4_4") (pintype "passive"))
    )
    (net (code "79") (name "/RESET2") (class "Default")
      (node (ref "IC3") (pin "24") (pinfunction "RESET_24") (pintype "input"))
      (node (ref "P3") (pin "5") (pinfunction "5_5") (pintype "passive"))
      (node (ref "RN4") (pin "1") (pinfunction "1_1") (pintype "passive"))
    )
    (net (code "80") (name "/RXD1") (class "Default")
      (node (ref "COMMUNICATION1") (pin "3") (pinfunction "3_3") (pintype "passive"))
      (node (ref "IC9") (pin "45") (pinfunction "(RXD1/INT2)PD2_45") (pintype "bidirectional"))
    )
    (net (code "81") (name "/RXD2") (class "Default")
      (node (ref "COMMUNICATION1") (pin "5") (pinfunction "5_5") (pintype "passive"))
      (node (ref "IC9") (pin "12") (pinfunction "PH0(RXD2)_12") (pintype "bidirectional"))
    )
    (net (code "82") (name "/RXD3") (class "Default")
      (node (ref "COMMUNICATION1") (pin "7") (pinfunction "7_7") (pintype "passive"))
      (node (ref "IC9") (pin "63") (pinfunction "PJ0(RXD3/PCINT9)_63") (pintype "bidirectional"))
    )
    (net (code "83") (name "/RXIN") (class "Default")
      (node (ref "IC6") (pin "6") (pinfunction "RXIN_6") (pintype "bidirectional"))
      (node (ref "RN5") (pin "2") (pinfunction "1_2") (pintype "passive"))
      (node (ref "U1") (pin "P$2") (pinfunction "RX-_P$2") (pintype "bidirectional"))
    )
    (net (code "84") (name "/RXIP") (class "Default")
      (node (ref "IC6") (pin "5") (pinfunction "RXIP_5") (pintype "bidirectional"))
      (node (ref "RN5") (pin "1") (pinfunction "1_1") (pintype "passive"))
      (node (ref "U1") (pin "P$1") (pinfunction "RX+_P$1") (pintype "bidirectional"))
    )
    (net (code "85") (name "/RXLED") (class "Default")
      (node (ref "IC3") (pin "10") (pinfunction "PD4_10") (pintype "bidirectional"))
      (node (ref "RN3") (pin "7") (pinfunction "2_7") (pintype "passive"))
    )
    (net (code "86") (name "/SCK2") (class "Default")
      (node (ref "IC3") (pin "15") (pinfunction "(SCLK)PB1_15") (pintype "bidirectional"))
      (node (ref "P3") (pin "3") (pinfunction "3_3") (pintype "passive"))
    )
    (net (code "87") (name "/SCL") (class "Default")
      (node (ref "COMMUNICATION1") (pin "1") (pinfunction "1_1") (pintype "passive"))
      (node (ref "IC9") (pin "43") (pinfunction "(SCL/INT0)PD0_43") (pintype "bidirectional"))
      (node (ref "JP4") (pin "2") (pinfunction "2_2") (pintype "passive"))
      (node (ref "PWMH") (pin "10") (pinfunction "10_10") (pintype "passive"))
      (node (ref "SJ6") (pin "1") (pinfunction "1_1") (pintype "passive"))
    )
    (net (code "88") (name "/SDA") (class "Default")
      (node (ref "COMMUNICATION1") (pin "2") (pinfunction "2_2") (pintype "passive"))
      (node (ref "IC9") (pin "44") (pinfunction "(SDA/INT1)PD1_44") (pintype "bidirectional"))
      (node (ref "JP4") (pin "3") (pinfunction "3_3") (pintype "passive"))
      (node (ref "PWMH") (pin "9") (pinfunction "9_9") (pintype "passive"))
      (node (ref "SJ5") (pin "1") (pinfunction "1_1") (pintype "passive"))
    )
    (net (code "89") (name "/SEN") (class "Default")
      (node (ref "IC6") (pin "31") (pinfunction "SEN_31") (pintype "bidirectional"))
      (node (ref "Q3") (pin "3") (pinfunction "D_3") (pintype "passive"))
      (node (ref "RN7") (pin "4") (pinfunction "1_4") (pintype "passive"))
    )
    (net (code "90") (name "/SPDLED") (class "Default")
      (node (ref "IC6") (pin "67") (pinfunction "SPDLED_67") (pintype "bidirectional"))
      (node (ref "RN2") (pin "3") (pinfunction "1_3") (pintype "passive"))
    )
    (net (code "91") (name "/TXD1") (class "Default")
      (node (ref "COMMUNICATION1") (pin "4") (pinfunction "4_4") (pintype "passive"))
      (node (ref "IC9") (pin "46") (pinfunction "(TXD1/INT3)PD3_46") (pintype "bidirectional"))
    )
    (net (code "92") (name "/TXD2") (class "Default")
      (node (ref "COMMUNICATION1") (pin "6") (pinfunction "6_6") (pintype "passive"))
      (node (ref "IC9") (pin "13") (pinfunction "PH1(TXD2)_13") (pintype "bidirectional"))
    )
    (net (code "93") (name "/TXD3") (class "Default")
      (node (ref "COMMUNICATION1") (pin "8") (pinfunction "8_8") (pintype "passive"))
      (node (ref "IC9") (pin "64") (pinfunction "PJ1(TXD3/PCINT10)_64") (pintype "bidirectional"))
    )
    (net (code "94") (name "/TXLED") (class "Default")
      (node (ref "IC3") (pin "11") (pinfunction "(XCK)PD5_11") (pintype "bidirectional"))
      (node (ref "RN3") (pin "8") (pinfunction "2_8") (pintype "passive"))
    )
    (net (code "95") (name "/TXON") (class "Default")
      (node (ref "IC6") (pin "9") (pinfunction "TXON_9") (pintype "bidirectional"))
      (node (ref "RN5") (pin "4") (pinfunction "1_4") (pintype "passive"))
      (node (ref "U1") (pin "P$6") (pinfunction "TX-_P$6") (pintype "bidirectional"))
    )
    (net (code "96") (name "/TXOP") (class "Default")
      (node (ref "IC6") (pin "8") (pinfunction "TXOP_8") (pintype "bidirectional"))
      (node (ref "RN5") (pin "3") (pinfunction "1_3") (pintype "passive"))
      (node (ref "U1") (pin "P$5") (pinfunction "TX+_P$5") (pintype "bidirectional"))
    )
    (net (code "97") (name "/USBRXD") (class "Default")
      (node (ref "IC3") (pin "9") (pinfunction "(TXD1)PD3_9") (pintype "bidirectional"))
      (node (ref "RN3") (pin "5") (pinfunction "2_5") (pintype "passive"))
    )
    (net (code "98") (name "/USBTXD") (class "Default")
      (node (ref "IC3") (pin "8") (pinfunction "(RXD1)PD2_8") (pintype "bidirectional"))
      (node (ref "RN3") (pin "6") (pinfunction "2_6") (pintype "passive"))
    )
    (net (code "99") (name "/USBVCC") (class "Default")
      (node (ref "F1") (pin "2") (pinfunction "2_2") (pintype "passive"))
      (node (ref "IC3") (pin "31") (pinfunction "UVCC_31") (pintype "power_in"))
      (node (ref "JP5") (pin "1") (pinfunction "1_1") (pintype "passive"))
    )
    (net (code "100") (name "/VIN") (class "Default")
      (node (ref "C36") (pin "1") (pinfunction "1_1") (pintype "passive"))
      (node (ref "D1") (pin "C") (pinfunction "C_C") (pintype "passive"))
      (node (ref "IC1") (pin "2") (pinfunction "IN_2") (pintype "power_in"))
      (node (ref "JP3") (pin "4") (pinfunction "VIN[4]_4") (pintype "passive"))
      (node (ref "JP6") (pin "1") (pinfunction "1_1") (pintype "passive"))
      (node (ref "R10") (pin "1") (pinfunction "1_1") (pintype "passive"))
    )
    (net (code "101") (name "/WIZRST") (class "Default")
      (node (ref "IC2") (pin "2") (pinfunction "/RESET_2") (pintype "output"))
      (node (ref "IC6") (pin "59") (pinfunction "/RESET_59") (pintype "bidirectional"))
    )
    (net (code "102") (name "/WRXLED") (class "Default")
      (node (ref "IC6") (pin "72") (pinfunction "RXLED_72") (pintype "bidirectional"))
      (node (ref "RN1") (pin "2") (pinfunction "1_2") (pintype "passive"))
    )
    (net (code "103") (name "/WTXLED") (class "Default")
      (node (ref "IC6") (pin "73") (pinfunction "TXLED_73") (pintype "bidirectional"))
      (node (ref "RN1") (pin "1") (pinfunction "1_1") (pintype "passive"))
    )
    (net (code "104") (name "/XTAL1") (class "Default")
      (node (ref "C21") (pin "2") (pinfunction "2_2") (pintype "passive"))
      (node (ref "IC9") (pin "34") (pinfunction "XTAL1_34") (pintype "input"))
      (node (ref "R7") (pin "1") (pinfunction "1_1") (pintype "passive"))
      (node (ref "X3") (pin "1") (pinfunction "1_1") (pintype "passive"))
    )
    (net (code "105") (name "/XTAL2") (class "Default")
      (node (ref "C20") (pin "2") (pinfunction "2_2") (pintype "passive"))
      (node (ref "IC9") (pin "33") (pinfunction "XTAL2_33") (pintype "output"))
      (node (ref "R7") (pin "2") (pinfunction "2_2") (pintype "passive"))
      (node (ref "X3") (pin "2") (pinfunction "2_2") (pintype "passive"))
    )
    (net (code "106") (name "5V") (class "Default")
      (node (ref "C12") (pin "1") (pinfunction "1_1") (pintype "passive"))
      (node (ref "C31") (pin "1") (pinfunction "1_1") (pintype "passive"))
      (node (ref "C33") (pin "1") (pinfunction "1_1") (pintype "passive"))
      (node (ref "C34") (pin "1") (pinfunction "1_1") (pintype "passive"))
      (node (ref "C6") (pin "2") (pinfunction "2_2") (pintype "passive"))
      (node (ref "C7") (pin "1") (pinfunction "1_1") (pintype "passive"))
      (node (ref "C9") (pin "1") (pinfunction "1_1") (pintype "passive"))
      (node (ref "IC2") (pin "4") (pinfunction "VCC_4") (pintype "power_in"))
      (node (ref "IC3") (pin "32") (pinfunction "AVCC_32") (pintype "power_in"))
      (node (ref "IC3") (pin "4") (pinfunction "VCC_4") (pintype "power_in"))
      (node (ref "IC4") (pin "6") (pinfunction "VCC_6") (pintype "power_in"))
      (node (ref "IC9") (pin "10") (pinfunction "VCC_10") (pintype "power_in"))
      (node (ref "IC9") (pin "100") (pinfunction "AVCC_100") (pintype "power_in"))
      (node (ref "IC9") (pin "31") (pinfunction "VCC1_31") (pintype "power_in"))
      (node (ref "IC9") (pin "61") (pinfunction "VCC2_61") (pintype "power_in"))
      (node (ref "IC9") (pin "80") (pinfunction "VCC3_80") (pintype "power_in"))
      (node (ref "ICSP") (pin "2") (pinfunction "2_2") (pintype "passive"))
      (node (ref "JP1") (pin "1") (pinfunction "1_1") (pintype "passive"))
      (node (ref "JP1") (pin "2") (pinfunction "2_2") (pintype "passive"))
      (node (ref "JP4") (pin "1") (pinfunction "1_1") (pintype "passive"))
      (node (ref "JP5") (pin "2") (pinfunction "2_2") (pintype "passive"))
      (node (ref "JP6") (pin "4") (pinfunction "4_4") (pintype "passive"))
      (node (ref "JP6") (pin "7") (pinfunction "7_7") (pintype "passive"))
      (node (ref "LED10") (pin "A") (pinfunction "A_A") (pintype "passive"))
      (node (ref "LED2") (pin "A") (pinfunction "A_A") (pintype "passive"))
      (node (ref "LED5") (pin "A") (pinfunction "A_A") (pintype "passive"))
      (node (ref "LED6") (pin "A") (pinfunction "A_A") (pintype "passive"))
      (node (ref "P3") (pin "2") (pinfunction "2_2") (pintype "passive"))
      (node (ref "R14") (pin "1") (pinfunction "1_1") (pintype "passive"))
      (node (ref "R15") (pin "1") (pinfunction "1_1") (pintype "passive"))
      (node (ref "REG1") (pin "3") (pinfunction "IN_3") (pintype "input"))
      (node (ref "REG2") (pin "3") (pinfunction "IN_3") (pintype "input"))
      (node (ref "RN4") (pin "7") (pinfunction "2_7") (pintype "passive"))
      (node (ref "RN4") (pin "8") (pinfunction "2_8") (pintype "passive"))
    )
    (net (code "107") (name "GND") (class "Default")
      (node (ref "C1") (pin "2") (pinfunction "2_2") (pintype "passive"))
      (node (ref "C10") (pin "C") (pinfunction "-_C") (pintype "passive"))
      (node (ref "C11") (pin "2") (pinfunction "2_2") (pintype "passive"))
      (node (ref "C12") (pin "2") (pinfunction "2_2") (pintype "passive"))
      (node (ref "C13") (pin "C") (pinfunction "-_C") (pintype "passive"))
      (node (ref "C15") (pin "2") (pinfunction "2_2") (pintype "passive"))
      (node (ref "C16") (pin "2") (pinfunction "2_2") (pintype "passive"))
      (node (ref "C17") (pin "2") (pinfunction "2_2") (pintype "passive"))
      (node (ref "C18") (pin "2") (pinfunction "2_2") (pintype "passive"))
      (node (ref "C2") (pin "1") (pinfunction "1_1") (pintype "passive"))
      (node (ref "C20") (pin "1") (pinfunction "1_1") (pintype "passive"))
      (node (ref "C21") (pin "1") (pinfunction "1_1") (pintype "passive"))
      (node (ref "C22") (pin "2") (pinfunction "2_2") (pintype "passive"))
      (node (ref "C23") (pin "2") (pinfunction "2_2") (pintype "passive"))
      (node (ref "C24") (pin "2") (pinfunction "2_2") (pintype "passive"))
      (node (ref "C25") (pin "2") (pinfunction "2_2") (pintype "passive"))
      (node (ref "C26") (pin "2") (pinfunction "2_2") (pintype "passive"))
      (node (ref "C27") (pin "2") (pinfunction "2_2") (pintype "passive"))
      (node (ref "C28") (pin "2") (pinfunction "2_2") (pintype "passive"))
      (node (ref "C29") (pin "2") (pinfunction "2_2") (pintype "passive"))
      (node (ref "C3") (pin "C") (pinfunction "-_C") (pintype "passive"))
      (node (ref "C30") (pin "2") (pinfunction "2_2") (pintype "passive"))
      (node (ref "C31") (pin "2") (pinfunction "2_2") (pintype "passive"))
      (node (ref "C33") (pin "2") (pinfunction "2_2") (pintype "passive"))
      (node (ref "C34") (pin "2") (pinfunction "2_2") (pintype "passive"))
      (node (ref "C35") (pin "2") (pinfunction "2_2") (pintype "passive"))
      (node (ref "C36") (pin "2") (pinfunction "2_2") (pintype "passive"))
      (node (ref "C37") (pin "2") (pinfunction "2_2") (pintype "passive"))
      (node (ref "C4") (pin "C") (pinfunction "-_C") (pintype "passive"))
      (node (ref "C6") (pin "1") (pinfunction "1_1") (pintype "passive"))
      (node (ref "C7") (pin "2") (pinfunction "2_2") (pintype "passive"))
      (node (ref "C8") (pin "1") (pinfunction "1_1") (pintype "passive"))
      (node (ref "C9") (pin "2") (pinfunction "2_2") (pintype "passive"))
      (node (ref "IC1") (pin "4") (pinfunction "GND_4") (pintype "power_in"))
      (node (ref "IC1") (pin "9") (pinfunction "TGND_9") (pintype "power_in"))
      (node (ref "IC2") (pin "1") (pinfunction "GND_1") (pintype "power_in"))
      (node (ref "IC3") (pin "3") (pinfunction "GND_3") (pintype "power_in"))
      (node (ref "IC3") (pin "EXP") (pinfunction "PAD_EXP") (pintype "power_in"))
      (node (ref "IC4") (pin "2") (pinfunction "GND_2") (pintype "power_in"))
      (node (ref "IC4") (pin "4") (pinfunction "A1_4") (pintype "input"))
      (node (ref "IC4") (pin "5") (pinfunction "A0_5") (pintype "input"))
      (node (ref "IC6") (pin "10") (pinfunction "GNDA1_10") (pintype "bidirectional"))
      (node (ref "IC6") (pin "13") (pinfunction "GNDD0_13") (pintype "bidirectional"))
      (node (ref "IC6") (pin "14") (pinfunction "GNDD1_14") (pintype "bidirectional"))
      (node (ref "IC6") (pin "17") (pinfunction "GNDD2_17") (pintype "bidirectional"))
      (node (ref "IC6") (pin "19") (pinfunction "DATA7_19") (pintype "bidirectional"))
      (node (ref "IC6") (pin "20") (pinfunction "DATA6_20") (pintype "bidirectional"))
      (node (ref "IC6") (pin "21") (pinfunction "DATA5_21") (pintype "bidirectional"))
      (node (ref "IC6") (pin "22") (pinfunction "DATA4_22") (pintype "bidirectional"))
      (node (ref "IC6") (pin "23") (pinfunction "DATA3_23") (pintype "bidirectional"))
      (node (ref "IC6") (pin "24") (pinfunction "DATA2_24") (pintype "bidirectional"))
      (node (ref "IC6") (pin "25") (pinfunction "DATA1_25") (pintype "bidirectional"))
      (node (ref "IC6") (pin "26") (pinfunction "DATA0_26") (pintype "bidirectional"))
      (node (ref "IC6") (pin "32") (pinfunction "GNDD3_32") (pintype "bidirectional"))
      (node (ref "IC6") (pin "34") (pinfunction "TEST_MODE3_34") (pintype "bidirectional"))
      (node (ref "IC6") (pin "35") (pinfunction "TEST_MODE2_35") (pintype "bidirectional"))
      (node (ref "IC6") (pin "36") (pinfunction "TEST_MODE1_36") (pintype "bidirectional"))
      (node (ref "IC6") (pin "37") (pinfunction "TEST_MODE0_37") (pintype "bidirectional"))
      (node (ref "IC6") (pin "38") (pinfunction "ADDR14_38") (pintype "bidirectional"))
      (node (ref "IC6") (pin "39") (pinfunction "ADDR13_39") (pintype "bidirectional"))
      (node (ref "IC6") (pin "4") (pinfunction "GNDA0_4") (pintype "bidirectional"))
      (node (ref "IC6") (pin "40") (pinfunction "ADDR12_40") (pintype "bidirectional"))
      (node (ref "IC6") (pin "41") (pinfunction "ADDR11_41") (pintype "bidirectional"))
      (node (ref "IC6") (pin "42") (pinfunction "ADDR10_42") (pintype "bidirectional"))
      (node (ref "IC6") (pin "43") (pinfunction "GNDD4_43") (pintype "bidirectional"))
      (node (ref "IC6") (pin "45") (pinfunction "ADDR9_45") (pintype "bidirectional"))
      (node (ref "IC6") (pin "46") (pinfunction "ADDR8_46") (pintype "bidirectional"))
      (node (ref "IC6") (pin "47") (pinfunction "ADDR7_47") (pintype "bidirectional"))
      (node (ref "IC6") (pin "48") (pinfunction "ADDR6_48") (pintype "bidirectional"))
      (node (ref "IC6") (pin "49") (pinfunction "ADDR5_49") (pintype "bidirectional"))
      (node (ref "IC6") (pin "50") (pinfunction "ADDR4_50") (pintype "bidirectional"))
      (node (ref "IC6") (pin "51") (pinfunction "ADDR3_51") (pintype "bidirectional"))
      (node (ref "IC6") (pin "52") (pinfunction "ADDR2_52") (pintype "bidirectional"))
      (node (ref "IC6") (pin "53") (pinfunction "ADDR1_53") (pintype "bidirectional"))
      (node (ref "IC6") (pin "54") (pinfunction "ADDR0_54") (pintype "bidirectional"))
      (node (ref "IC6") (pin "63") (pinfunction "OPMODE0_63") (pintype "bidirectional"))
      (node (ref "IC6") (pin "64") (pinfunction "OPMODE1_64") (pintype "bidirectional"))
      (node (ref "IC6") (pin "65") (pinfunction "OPMODE2_65") (pintype "bidirectional"))
      (node (ref "IC6") (pin "68") (pinfunction "GNDD5_68") (pintype "bidirectional"))
      (node (ref "IC6") (pin "77") (pinfunction "GNDA2_77") (pintype "bidirectional"))
      (node (ref "IC9") (pin "11") (pinfunction "GND_11") (pintype "power_in"))
      (node (ref "IC9") (pin "32") (pinfunction "GND1_32") (pintype "power_in"))
      (node (ref "IC9") (pin "62") (pinfunction "GND2_62") (pintype "power_in"))
      (node (ref "IC9") (pin "81") (pinfunction "GND3_81") (pintype "power_in"))
      (node (ref "IC9") (pin "99") (pinfunction "AGND_99") (pintype "power_in"))
      (node (ref "ICSP") (pin "6") (pinfunction "6_6") (pintype "passive"))
      (node (ref "J1") (pin "GND") (pinfunction "GND_GND") (pintype "bidirectional"))
      (node (ref "J1") (pin "GNDBREAK") (pinfunction "GNDBREAK_GNDBREAK") (pintype "bidirectional"))
      (node (ref "JP2") (pin "1") (pinfunction "1_1") (pintype "passive"))
      (node (ref "JP2") (pin "2") (pinfunction "2_2") (pintype "passive"))
      (node (ref "JP3") (pin "1") (pinfunction "GND[1]_1") (pintype "passive"))
      (node (ref "JP3") (pin "MNT1") (pinfunction "MNT1_MNT1") (pintype "passive"))
      (node (ref "JP3") (pin "MNT2") (pinfunction "MNT2_MNT2") (pintype "passive"))
      (node (ref "JP4") (pin "4") (pinfunction "4_4") (pintype "passive"))
      (node (ref "JP6") (pin "2") (pinfunction "2_2") (pintype "passive"))
      (node (ref "JP6") (pin "3") (pinfunction "3_3") (pintype "passive"))
      (node (ref "P3") (pin "6") (pinfunction "6_6") (pintype "passive"))
      (node (ref "P4") (pin "6") (pinfunction "GND_6") (pintype "bidirectional"))
      (node (ref "P4") (pin "GND1") (pinfunction "SHIELD1_GND1") (pintype "bidirectional"))
      (node (ref "P4") (pin "GND2") (pinfunction "SHIELD2_GND2") (pintype "bidirectional"))
      (node (ref "P4") (pin "GND3") (pinfunction "CD1_GND3") (pintype "bidirectional"))
      (node (ref "P4") (pin "GND4") (pinfunction "CD2_GND4") (pintype "bidirectional"))
      (node (ref "PWMH") (pin "7") (pinfunction "7_7") (pintype "passive"))
      (node (ref "Q2") (pin "2") (pinfunction "S_2") (pintype "passive"))
      (node (ref "Q3") (pin "2") (pinfunction "S_2") (pintype "passive"))
      (node (ref "R11") (pin "1") (pinfunction "1_1") (pintype "passive"))
      (node (ref "R13") (pin "1") (pinfunction "1_1") (pintype "passive"))
      (node (ref "R6") (pin "1") (pinfunction "1_1") (pintype "passive"))
      (node (ref "REG1") (pin "1") (pinfunction "ADJ_1") (pintype "input"))
      (node (ref "REG2") (pin "1") (pinfunction "GND_1") (pintype "input"))
      (node (ref "RN8") (pin "1") (pinfunction "1_1") (pintype "passive"))
      (node (ref "RN8") (pin "2") (pinfunction "1_2") (pintype "passive"))
      (node (ref "RN8") (pin "3") (pinfunction "1_3") (pintype "passive"))
      (node (ref "S1") (pin "1") (pinfunction "1_1") (pintype "passive"))
      (node (ref "S1") (pin "2") (pinfunction "2_2") (pintype "passive"))
      (node (ref "SJ1") (pin "2") (pinfunction "2_2") (pintype "passive"))
      (node (ref "SJ2") (pin "1") (pinfunction "1_1") (pintype "passive"))
      (node (ref "U1") (pin "GND1") (pinfunction "GND1_GND1") (pintype "bidirectional"))
      (node (ref "U1") (pin "GND2") (pinfunction "GND2_GND2") (pintype "bidirectional"))
    )
    (net (code "108") (name "Net-(C1-Pad1)") (class "Default")
      (node (ref "C1") (pin "1") (pinfunction "1_1") (pintype "passive"))
      (node (ref "R9") (pin "1") (pinfunction "1_1") (pintype "passive"))
    )
    (net (code "109") (name "Net-(C8-Pad2)") (class "Default")
      (node (ref "C8") (pin "2") (pinfunction "2_2") (pintype "passive"))
      (node (ref "R1") (pin "1") (pinfunction "1_1") (pintype "passive"))
      (node (ref "R2") (pin "2") (pinfunction "2_2") (pintype "passive"))
      (node (ref "X1") (pin "1") (pinfunction "1_1") (pintype "passive"))
    )
    (net (code "110") (name "Net-(C19-Pad1)") (class "Default")
      (node (ref "C19") (pin "1") (pinfunction "1_1") (pintype "passive"))
      (node (ref "JP7") (pin "1") (pinfunction "1_1") (pintype "passive"))
      (node (ref "SJ3") (pin "2") (pinfunction "2_2") (pintype "passive"))
    )
    (net (code "111") (name "Net-(D1-PadA)") (class "Default")
      (node (ref "D1") (pin "A") (pinfunction "A_A") (pintype "passive"))
      (node (ref "J1") (pin "PWR") (pinfunction "PWR_PWR") (pintype "bidirectional"))
    )
    (net (code "112") (name "Net-(F1-Pad1)") (class "Default")
      (node (ref "F1") (pin "1") (pinfunction "1_1") (pintype "passive"))
      (node (ref "P1") (pin "VBUS") (pinfunction "VBUS_VBUS") (pintype "bidirectional"))
    )
    (net (code "113") (name "Net-(IC1-BS)") (class "Default")
      (node (ref "C32") (pin "2") (pinfunction "2_2") (pintype "passive"))
      (node (ref "IC1") (pin "1") (pinfunction "BS_1") (pintype "bidirectional"))
    )
    (net (code "114") (name "Net-(IC1-COMP)") (class "Default")
      (node (ref "C35") (pin "1") (pinfunction "1_1") (pintype "passive"))
      (node (ref "IC1") (pin "6") (pinfunction "COMP_6") (pintype "bidirectional"))
      (node (ref "R9") (pin "2") (pinfunction "2_2") (pintype "passive"))
    )
    (net (code "115") (name "Net-(IC1-EN)") (class "Default")
      (node (ref "IC1") (pin "7") (pinfunction "EN_7") (pintype "input"))
      (node (ref "R10") (pin "2") (pinfunction "2_2") (pintype "passive"))
    )
    (net (code "116") (name "Net-(IC1-FB)") (class "Default")
      (node (ref "IC1") (pin "5") (pinfunction "FB_5") (pintype "bidirectional"))
      (node (ref "R11") (pin "2") (pinfunction "2_2") (pintype "passive"))
      (node (ref "R12") (pin "1") (pinfunction "1_1") (pintype "passive"))
    )
    (net (code "117") (name "Net-(IC1-SS)") (class "Default")
      (node (ref "C27") (pin "1") (pinfunction "1_1") (pintype "passive"))
      (node (ref "IC1") (pin "8") (pinfunction "SS_8") (pintype "bidirectional"))
    )
    (net (code "118") (name "Net-(IC1-SW)") (class "Default")
      (node (ref "C32") (pin "1") (pinfunction "1_1") (pintype "passive"))
      (node (ref "IC1") (pin "3") (pinfunction "SW_3") (pintype "bidirectional"))
      (node (ref "L4") (pin "1") (pinfunction "1_1") (pintype "bidirectional"))
    )
    (net (code "119") (name "Net-(IC3-UCAP)") (class "Default")
      (node (ref "C11") (pin "1") (pinfunction "1_1") (pintype "passive"))
      (node (ref "IC3") (pin "27") (pinfunction "UCAP_27") (pintype "passive"))
    )
    (net (code "120") (name "Net-(IC3-UGND)") (class "Default")
      (node (ref "IC3") (pin "28") (pinfunction "UGND_28") (pintype "power_in"))
      (node (ref "L3") (pin "2") (pinfunction "2_2") (pintype "passive"))
      (node (ref "P1") (pin "GND") (pinfunction "GND_GND") (pintype "bidirectional"))
      (node (ref "SJ1") (pin "1") (pinfunction "1_1") (pintype "passive"))
    )
    (net (code "121") (name "Net-(IC3-XTAL1)") (class "Default")
      (node (ref "IC3") (pin "1") (pinfunction "XTAL1_1") (pintype "bidirectional"))
      (node (ref "R2") (pin "1") (pinfunction "1_1") (pintype "passive"))
    )
    (net (code "122") (name "Net-(IC3-XTAL2)") (class "Default")
      (node (ref "C2") (pin "2") (pinfunction "2_2") (pintype "passive"))
      (node (ref "IC3") (pin "2") (pinfunction "XTAL2_2") (pintype "bidirectional"))
      (node (ref "R1") (pin "2") (pinfunction "2_2") (pintype "passive"))
      (node (ref "X1") (pin "2") (pinfunction "2_2") (pintype "passive"))
    )
    (net (code "123") (name "Net-(IC4-SCL)") (class "Default")
      (node (ref "IC4") (pin "1") (pinfunction "SCL_1") (pintype "bidirectional"))
      (node (ref "R15") (pin "2") (pinfunction "2_2") (pintype "passive"))
      (node (ref "SJ6") (pin "2") (pinfunction "2_2") (pintype "passive"))
    )
    (net (code "124") (name "Net-(IC4-SDA)") (class "Default")
      (node (ref "IC4") (pin "3") (pinfunction "SDA_3") (pintype "bidirectional"))
      (node (ref "R14") (pin "2") (pinfunction "2_2") (pintype "passive"))
      (node (ref "SJ5") (pin "2") (pinfunction "2_2") (pintype "passive"))
    )
    (net (code "125") (name "Net-(IC6-RSET_BG)") (class "Default")
      (node (ref "IC6") (pin "1") (pinfunction "RSET_BG_1") (pintype "bidirectional"))
      (node (ref "R6") (pin "2") (pinfunction "2_2") (pintype "passive"))
    )
    (net (code "126") (name "Net-(IC6-XTLN)") (class "Default")
      (node (ref "C16") (pin "1") (pinfunction "1_1") (pintype "passive"))
      (node (ref "IC6") (pin "75") (pinfunction "XTLN_75") (pintype "bidirectional"))
      (node (ref "R3") (pin "2") (pinfunction "2_2") (pintype "passive"))
      (node (ref "X2") (pin "2") (pinfunction "2_2") (pintype "passive"))
    )
    (net (code "127") (name "Net-(IC6-XTLP)") (class "Default")
      (node (ref "C15") (pin "1") (pinfunction "1_1") (pintype "passive"))
      (node (ref "IC6") (pin "76") (pinfunction "XTLP_76") (pintype "bidirectional"))
      (node (ref "R3") (pin "1") (pinfunction "1_1") (pintype "passive"))
      (node (ref "X2") (pin "1") (pinfunction "1_1") (pintype "passive"))
    )
    (net (code "128") (name "Net-(IC6-{slash}CS)") (class "Default")
      (node (ref "IC6") (pin "55") (pinfunction "/CS_55") (pintype "bidirectional"))
      (node (ref "IC6") (pin "57") (pinfunction "/WR_57") (pintype "bidirectional"))
      (node (ref "IC6") (pin "58") (pinfunction "/RD_58") (pintype "bidirectional"))
      (node (ref "RN7") (pin "2") (pinfunction "1_2") (pintype "passive"))
    )
    (net (code "129") (name "Net-(IC6-{slash}INT)") (class "Default")
      (node (ref "IC6") (pin "56") (pinfunction "/INT_56") (pintype "bidirectional"))
      (node (ref "SJ4") (pin "2") (pinfunction "2_2") (pintype "passive"))
    )
    (net (code "130") (name "Net-(JP3-V+[3])") (class "Default")
      (node (ref "JP3") (pin "3") (pinfunction "V+[3]_3") (pintype "passive"))
      (node (ref "U1") (pin "P$9") (pinfunction "V+_P$9") (pintype "bidirectional"))
    )
    (net (code "131") (name "Net-(JP3-V-[2])") (class "Default")
      (node (ref "JP3") (pin "2") (pinfunction "V-[2]_2") (pintype "passive"))
      (node (ref "U1") (pin "P$10") (pinfunction "V-_P$10") (pintype "bidirectional"))
    )
    (net (code "132") (name "Net-(L3-Pad1)") (class "Default")
      (node (ref "L3") (pin "1") (pinfunction "1_1") (pintype "passive"))
      (node (ref "P1") (pin "FIX1") (pinfunction "FIX1_FIX1") (pintype "bidirectional"))
      (node (ref "P1") (pin "FIX2") (pinfunction "FIX2_FIX2") (pintype "bidirectional"))
      (node (ref "P1") (pin "PIN1") (pinfunction "PIN1_PIN1") (pintype "bidirectional"))
      (node (ref "P1") (pin "PIN2") (pinfunction "PIN2_PIN2") (pintype "bidirectional"))
      (node (ref "P1") (pin "TAB1") (pinfunction "TAB1_TAB1") (pintype "bidirectional"))
      (node (ref "P1") (pin "TAB2") (pinfunction "TAB2_TAB2") (pintype "bidirectional"))
      (node (ref "Z1") (pin "2") (pinfunction "2_2") (pintype "passive"))
      (node (ref "Z2") (pin "2") (pinfunction "2_2") (pintype "passive"))
    )
    (net (code "133") (name "Net-(LED2-PadC)") (class "Default")
      (node (ref "LED2") (pin "C") (pinfunction "C_C") (pintype "passive"))
      (node (ref "R13") (pin "2") (pinfunction "2_2") (pintype "passive"))
    )
    (net (code "134") (name "Net-(LED5-PadC)") (class "Default")
      (node (ref "LED5") (pin "C") (pinfunction "C_C") (pintype "passive"))
      (node (ref "RN3") (pin "1") (pinfunction "1_1") (pintype "passive"))
    )
    (net (code "135") (name "Net-(LED10-PadC)") (class "Default")
      (node (ref "LED10") (pin "C") (pinfunction "C_C") (pintype "passive"))
      (node (ref "R8") (pin "2") (pinfunction "2_2") (pintype "passive"))
    )
    (net (code "136") (name "Net-(P1-PadD+)") (class "Default")
      (node (ref "P1") (pin "D+") (pinfunction "D+_D+") (pintype "bidirectional"))
      (node (ref "R5") (pin "2") (pinfunction "2_2") (pintype "passive"))
      (node (ref "Z1") (pin "1") (pinfunction "1_1") (pintype "passive"))
    )
    (net (code "137") (name "Net-(P1-PadD-)") (class "Default")
      (node (ref "P1") (pin "D-") (pinfunction "D-_D-") (pintype "bidirectional"))
      (node (ref "R4") (pin "2") (pinfunction "2_2") (pintype "passive"))
      (node (ref "Z2") (pin "1") (pinfunction "1_1") (pintype "passive"))
    )
    (net (code "138") (name "Net-(P4-CS)") (class "Default")
      (node (ref "P4") (pin "2") (pinfunction "CS_2") (pintype "bidirectional"))
      (node (ref "RN6") (pin "2") (pinfunction "1_2") (pintype "passive"))
      (node (ref "RN8") (pin "8") (pinfunction "2_8") (pintype "passive"))
    )
    (net (code "139") (name "Net-(P4-DI)") (class "Default")
      (node (ref "P4") (pin "3") (pinfunction "DI_3") (pintype "bidirectional"))
      (node (ref "RN6") (pin "3") (pinfunction "1_3") (pintype "passive"))
      (node (ref "RN8") (pin "7") (pinfunction "2_7") (pintype "passive"))
    )
    (net (code "140") (name "Net-(P4-SCK)") (class "Default")
      (node (ref "P4") (pin "5") (pinfunction "SCK_5") (pintype "bidirectional"))
      (node (ref "RN6") (pin "4") (pinfunction "1_4") (pintype "passive"))
      (node (ref "RN8") (pin "6") (pinfunction "2_6") (pintype "passive"))
    )
    (net (code "141") (name "Net-(Q2-D)") (class "Default")
      (node (ref "Q2") (pin "3") (pinfunction "D_3") (pintype "passive"))
      (node (ref "R8") (pin "1") (pinfunction "1_1") (pintype "passive"))
    )
    (net (code "142") (name "Net-(RN1A-2)") (class "Default")
      (node (ref "LED1") (pin "C") (pinfunction "C_C") (pintype "passive"))
      (node (ref "RN1") (pin "8") (pinfunction "2_8") (pintype "passive"))
    )
    (net (code "143") (name "Net-(RN1B-2)") (class "Default")
      (node (ref "LED3") (pin "C") (pinfunction "C_C") (pintype "passive"))
      (node (ref "RN1") (pin "7") (pinfunction "2_7") (pintype "passive"))
    )
    (net (code "144") (name "Net-(RN1C-2)") (class "Default")
      (node (ref "LED4") (pin "C") (pinfunction "C_C") (pintype "passive"))
      (node (ref "RN1") (pin "6") (pinfunction "2_6") (pintype "passive"))
    )
    (net (code "145") (name "Net-(RN1D-2)") (class "Default")
      (node (ref "LED7") (pin "C") (pinfunction "C_C") (pintype "passive"))
      (node (ref "RN1") (pin "5") (pinfunction "2_5") (pintype "passive"))
    )
    (net (code "146") (name "Net-(RN2B-1)") (class "Default")
      (node (ref "RN2") (pin "2") (pinfunction "1_2") (pintype "passive"))
      (node (ref "U1") (pin "P$12") (pinfunction "Y-_P$12") (pintype "bidirectional"))
    )
    (net (code "147") (name "Net-(RN2C-2)") (class "Default")
      (node (ref "LED8") (pin "C") (pinfunction "C_C") (pintype "passive"))
      (node (ref "RN2") (pin "6") (pinfunction "2_6") (pintype "passive"))
    )
    (net (code "148") (name "Net-(RN2D-2)") (class "Default")
      (node (ref "LED9") (pin "C") (pinfunction "C_C") (pintype "passive"))
      (node (ref "RN2") (pin "5") (pinfunction "2_5") (pintype "passive"))
    )
    (net (code "149") (name "Net-(RN3B-1)") (class "Default")
      (node (ref "LED6") (pin "C") (pinfunction "C_C") (pintype "passive"))
      (node (ref "RN3") (pin "2") (pinfunction "1_2") (pintype "passive"))
    )
    (net (code "150") (name "Net-(RN5A-2)") (class "Default")
      (node (ref "C23") (pin "1") (pinfunction "1_1") (pintype "passive"))
      (node (ref "RN5") (pin "7") (pinfunction "2_7") (pintype "passive"))
      (node (ref "RN5") (pin "8") (pinfunction "2_8") (pintype "passive"))
    )
    (net (code "151") (name "Net-(RN5C-2)") (class "Default")
      (node (ref "C24") (pin "1") (pinfunction "1_1") (pintype "passive"))
      (node (ref "RN5") (pin "5") (pinfunction "2_5") (pintype "passive"))
      (node (ref "RN5") (pin "6") (pinfunction "2_6") (pintype "passive"))
    )
    (net (code "152") (name "Net-(U1-G-)") (class "Default")
      (node (ref "RN2") (pin "1") (pinfunction "1_1") (pintype "passive"))
      (node (ref "U1") (pin "P$14") (pinfunction "G-_P$14") (pintype "bidirectional"))
    )
    (net (code "153") (name "unconnected-(IC3-(RTS)PD6-Pad12)") (class "Default")
      (node (ref "IC3") (pin "12") (pinfunction "(RTS)PD6_12") (pintype "bidirectional"))
    )
    (net (code "154") (name "unconnected-(IC3-(SS)PB0-Pad14)") (class "Default")
      (node (ref "IC3") (pin "14") (pinfunction "(SS)PB0_14") (pintype "bidirectional"))
    )
    (net (code "155") (name "unconnected-(IC3-PB4-Pad18)") (class "Default")
      (node (ref "IC3") (pin "18") (pinfunction "PB4_18") (pintype "bidirectional"))
    )
    (net (code "156") (name "unconnected-(IC3-PB5-Pad19)") (class "Default")
      (node (ref "IC3") (pin "19") (pinfunction "PB5_19") (pintype "bidirectional"))
    )
    (net (code "157") (name "unconnected-(IC3-PB6-Pad20)") (class "Default")
      (node (ref "IC3") (pin "20") (pinfunction "PB6_20") (pintype "bidirectional"))
    )
    (net (code "158") (name "unconnected-(IC3-PB7-Pad21)") (class "Default")
      (node (ref "IC3") (pin "21") (pinfunction "PB7_21") (pintype "bidirectional"))
    )
    (net (code "159") (name "unconnected-(IC3-PC2-Pad5)") (class "Default")
      (node (ref "IC3") (pin "5") (pinfunction "PC2_5") (pintype "bidirectional"))
    )
    (net (code "160") (name "unconnected-(IC3-PC4-Pad26)") (class "Default")
      (node (ref "IC3") (pin "26") (pinfunction "PC4_26") (pintype "bidirectional"))
    )
    (net (code "161") (name "unconnected-(IC3-PC5-Pad25)") (class "Default")
      (node (ref "IC3") (pin "25") (pinfunction "PC5_25") (pintype "bidirectional"))
    )
    (net (code "162") (name "unconnected-(IC3-PC6-Pad23)") (class "Default")
      (node (ref "IC3") (pin "23") (pinfunction "PC6_23") (pintype "bidirectional"))
    )
    (net (code "163") (name "unconnected-(IC3-PC7-Pad22)") (class "Default")
      (node (ref "IC3") (pin "22") (pinfunction "PC7_22") (pintype "bidirectional"))
    )
    (net (code "164") (name "unconnected-(IC3-PD0-Pad6)") (class "Default")
      (node (ref "IC3") (pin "6") (pinfunction "PD0_6") (pintype "bidirectional"))
    )
    (net (code "165") (name "unconnected-(IC3-PD1-Pad7)") (class "Default")
      (node (ref "IC3") (pin "7") (pinfunction "PD1_7") (pintype "bidirectional"))
    )
    (net (code "166") (name "unconnected-(IC6-NC0-Pad3)") (class "Default")
      (node (ref "IC6") (pin "3") (pinfunction "NC0_3") (pintype "bidirectional"))
    )
    (net (code "167") (name "unconnected-(IC6-NC1-Pad60)") (class "Default")
      (node (ref "IC6") (pin "60") (pinfunction "NC1_60") (pintype "bidirectional"))
    )
    (net (code "168") (name "unconnected-(IC6-NC2-Pad61)") (class "Default")
      (node (ref "IC6") (pin "61") (pinfunction "NC2_61") (pintype "bidirectional"))
    )
    (net (code "169") (name "unconnected-(IC6-NC3-Pad62)") (class "Default")
      (node (ref "IC6") (pin "62") (pinfunction "NC3_62") (pintype "bidirectional"))
    )
    (net (code "170") (name "unconnected-(IC6-NC4-Pad78)") (class "Default")
      (node (ref "IC6") (pin "78") (pinfunction "NC4_78") (pintype "bidirectional"))
    )
    (net (code "171") (name "unconnected-(IC6-NC5-Pad79)") (class "Default")
      (node (ref "IC6") (pin "79") (pinfunction "NC5_79") (pintype "bidirectional"))
    )
    (net (code "172") (name "unconnected-(IC6-NC6-Pad80)") (class "Default")
      (node (ref "IC6") (pin "80") (pinfunction "NC6_80") (pintype "bidirectional"))
    )
    (net (code "173") (name "unconnected-(IC9-(CLKO{slash}ICP3{slash}INT7)PE7-Pad9)") (class "Default")
      (node (ref "IC9") (pin "9") (pinfunction "(CLKO/ICP3/INT7)PE7_9") (pintype "bidirectional"))
    )
    (net (code "174") (name "unconnected-(IC9-(ICP1)PD4-Pad47)") (class "Default")
      (node (ref "IC9") (pin "47") (pinfunction "(ICP1)PD4_47") (pintype "bidirectional"))
    )
    (net (code "175") (name "unconnected-(IC9-(T1)PD6-Pad49)") (class "Default")
      (node (ref "IC9") (pin "49") (pinfunction "(T1)PD6_49") (pintype "bidirectional"))
    )
    (net (code "176") (name "unconnected-(IC9-(T3{slash}INT6)PE6-Pad8)") (class "Default")
      (node (ref "IC9") (pin "8") (pinfunction "(T3/INT6)PE6_8") (pintype "bidirectional"))
    )
    (net (code "177") (name "unconnected-(IC9-(TOSC1)PG4-Pad29)") (class "Default")
      (node (ref "IC9") (pin "29") (pinfunction "(TOSC1)PG4_29") (pintype "bidirectional"))
    )
    (net (code "178") (name "unconnected-(IC9-(TOSC2)PG3-Pad28)") (class "Default")
      (node (ref "IC9") (pin "28") (pinfunction "(TOSC2)PG3_28") (pintype "bidirectional"))
    )
    (net (code "179") (name "unconnected-(IC9-(XCK0{slash}AIN0)PE2-Pad4)") (class "Default")
      (node (ref "IC9") (pin "4") (pinfunction "(XCK0/AIN0)PE2_4") (pintype "bidirectional"))
    )
    (net (code "180") (name "unconnected-(IC9-(XCK1)PD5-Pad48)") (class "Default")
      (node (ref "IC9") (pin "48") (pinfunction "(XCK1)PD5_48") (pintype "bidirectional"))
    )
    (net (code "181") (name "unconnected-(IC9-PH2(XCK2)-Pad14)") (class "Default")
      (node (ref "IC9") (pin "14") (pinfunction "PH2(XCK2)_14") (pintype "bidirectional"))
    )
    (net (code "182") (name "unconnected-(IC9-PH7(T4)-Pad27)") (class "Default")
      (node (ref "IC9") (pin "27") (pinfunction "PH7(T4)_27") (pintype "bidirectional"))
    )
    (net (code "183") (name "unconnected-(IC9-PJ2(XCK3{slash}PCINT11)-Pad65)") (class "Default")
      (node (ref "IC9") (pin "65") (pinfunction "PJ2(XCK3/PCINT11)_65") (pintype "bidirectional"))
    )
    (net (code "184") (name "unconnected-(IC9-PJ3(PCINT12)-Pad66)") (class "Default")
      (node (ref "IC9") (pin "66") (pinfunction "PJ3(PCINT12)_66") (pintype "bidirectional"))
    )
    (net (code "185") (name "unconnected-(IC9-PJ4(PCINT13)-Pad67)") (class "Default")
      (node (ref "IC9") (pin "67") (pinfunction "PJ4(PCINT13)_67") (pintype "bidirectional"))
    )
    (net (code "186") (name "unconnected-(IC9-PJ5(PCINT14)-Pad68)") (class "Default")
      (node (ref "IC9") (pin "68") (pinfunction "PJ5(PCINT14)_68") (pintype "bidirectional"))
    )
    (net (code "187") (name "unconnected-(IC9-PJ6(PCINT15)-Pad69)") (class "Default")
      (node (ref "IC9") (pin "69") (pinfunction "PJ6(PCINT15)_69") (pintype "bidirectional"))
    )
    (net (code "188") (name "unconnected-(IC9-PJ7-Pad79)") (class "Default")
      (node (ref "IC9") (pin "79") (pinfunction "PJ7_79") (pintype "bidirectional"))
    )
    (net (code "189") (name "unconnected-(P1-PadID)") (class "Default")
      (node (ref "P1") (pin "ID") (pinfunction "ID_ID") (pintype "bidirectional"))
    )
    (net (code "190") (name "unconnected-(P4-NC-Pad1)") (class "Default")
      (node (ref "P4") (pin "1") (pinfunction "NC_1") (pintype "bidirectional"))
    )
    (net (code "191") (name "unconnected-(P4-RSV-Pad8)") (class "Default")
      (node (ref "P4") (pin "8") (pinfunction "RSV_8") (pintype "bidirectional"))
    )
    (net (code "192") (name "unconnected-(RN6-Pad1)") (class "Default")
      (node (ref "RN6") (pin "1") (pinfunction "1_1") (pintype "passive"))
    )
    (net (code "193") (name "unconnected-(RN6A-2-Pad8)") (class "Default")
      (node (ref "RN6") (pin "8") (pinfunction "2_8") (pintype "passive"))
    )
    (net (code "194") (name "unconnected-(RN7-Pad1)") (class "Default")
      (node (ref "RN7") (pin "1") (pinfunction "1_1") (pintype "passive"))
    )
    (net (code "195") (name "unconnected-(RN7A-2-Pad8)") (class "Default")
      (node (ref "RN7") (pin "8") (pinfunction "2_8") (pintype "passive"))
    )
    (net (code "196") (name "unconnected-(RN7C-1-Pad3)") (class "Default")
      (node (ref "RN7") (pin "3") (pinfunction "1_3") (pintype "passive"))
    )
    (net (code "197") (name "unconnected-(RN7C-2-Pad6)") (class "Default")
      (node (ref "RN7") (pin "6") (pinfunction "2_6") (pintype "passive"))
    )
    (net (code "198") (name "unconnected-(RN8D-1-Pad4)") (class "Default")
      (node (ref "RN8") (pin "4") (pinfunction "1_4") (pintype "passive"))
    )
    (net (code "199") (name "unconnected-(RN8D-2-Pad5)") (class "Default")
      (node (ref "RN8") (pin "5") (pinfunction "2_5") (pintype "passive"))
    )
  )
)
